# PixelScreen_WS2812B_4layer.net
KiCad netlist of a schematic drawn in EasyEDA Pro
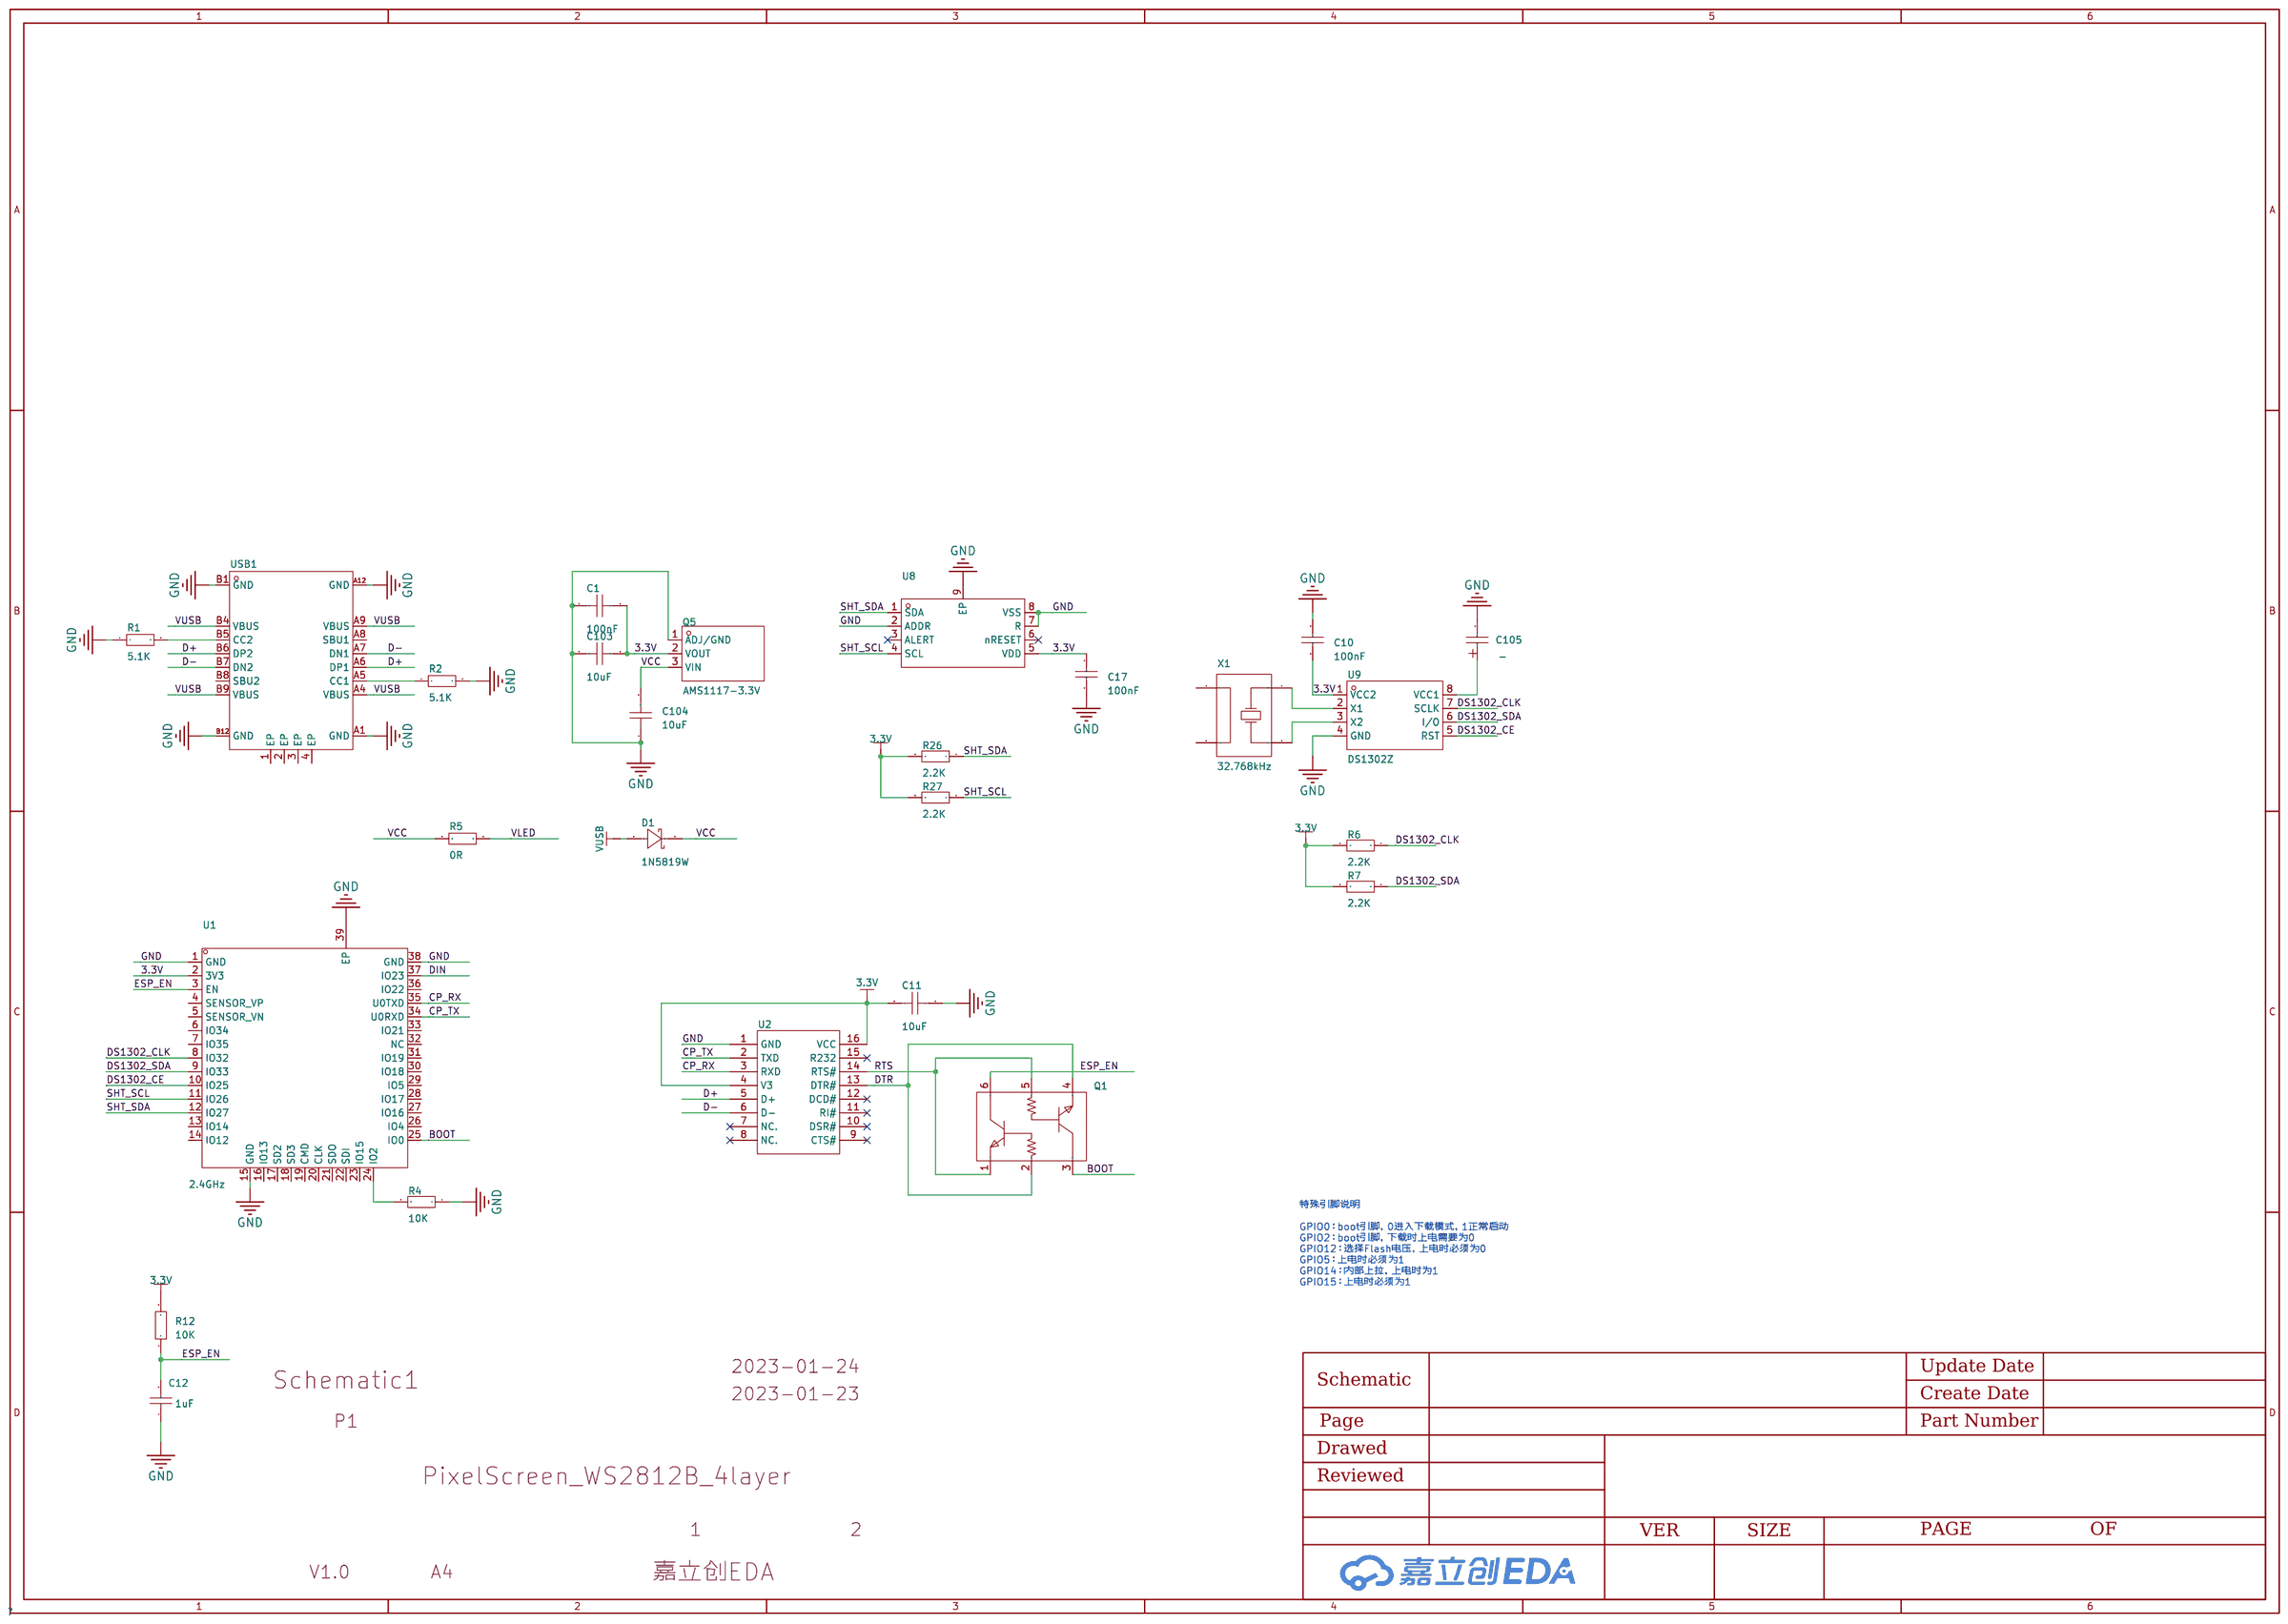
[diagram p0: P1]
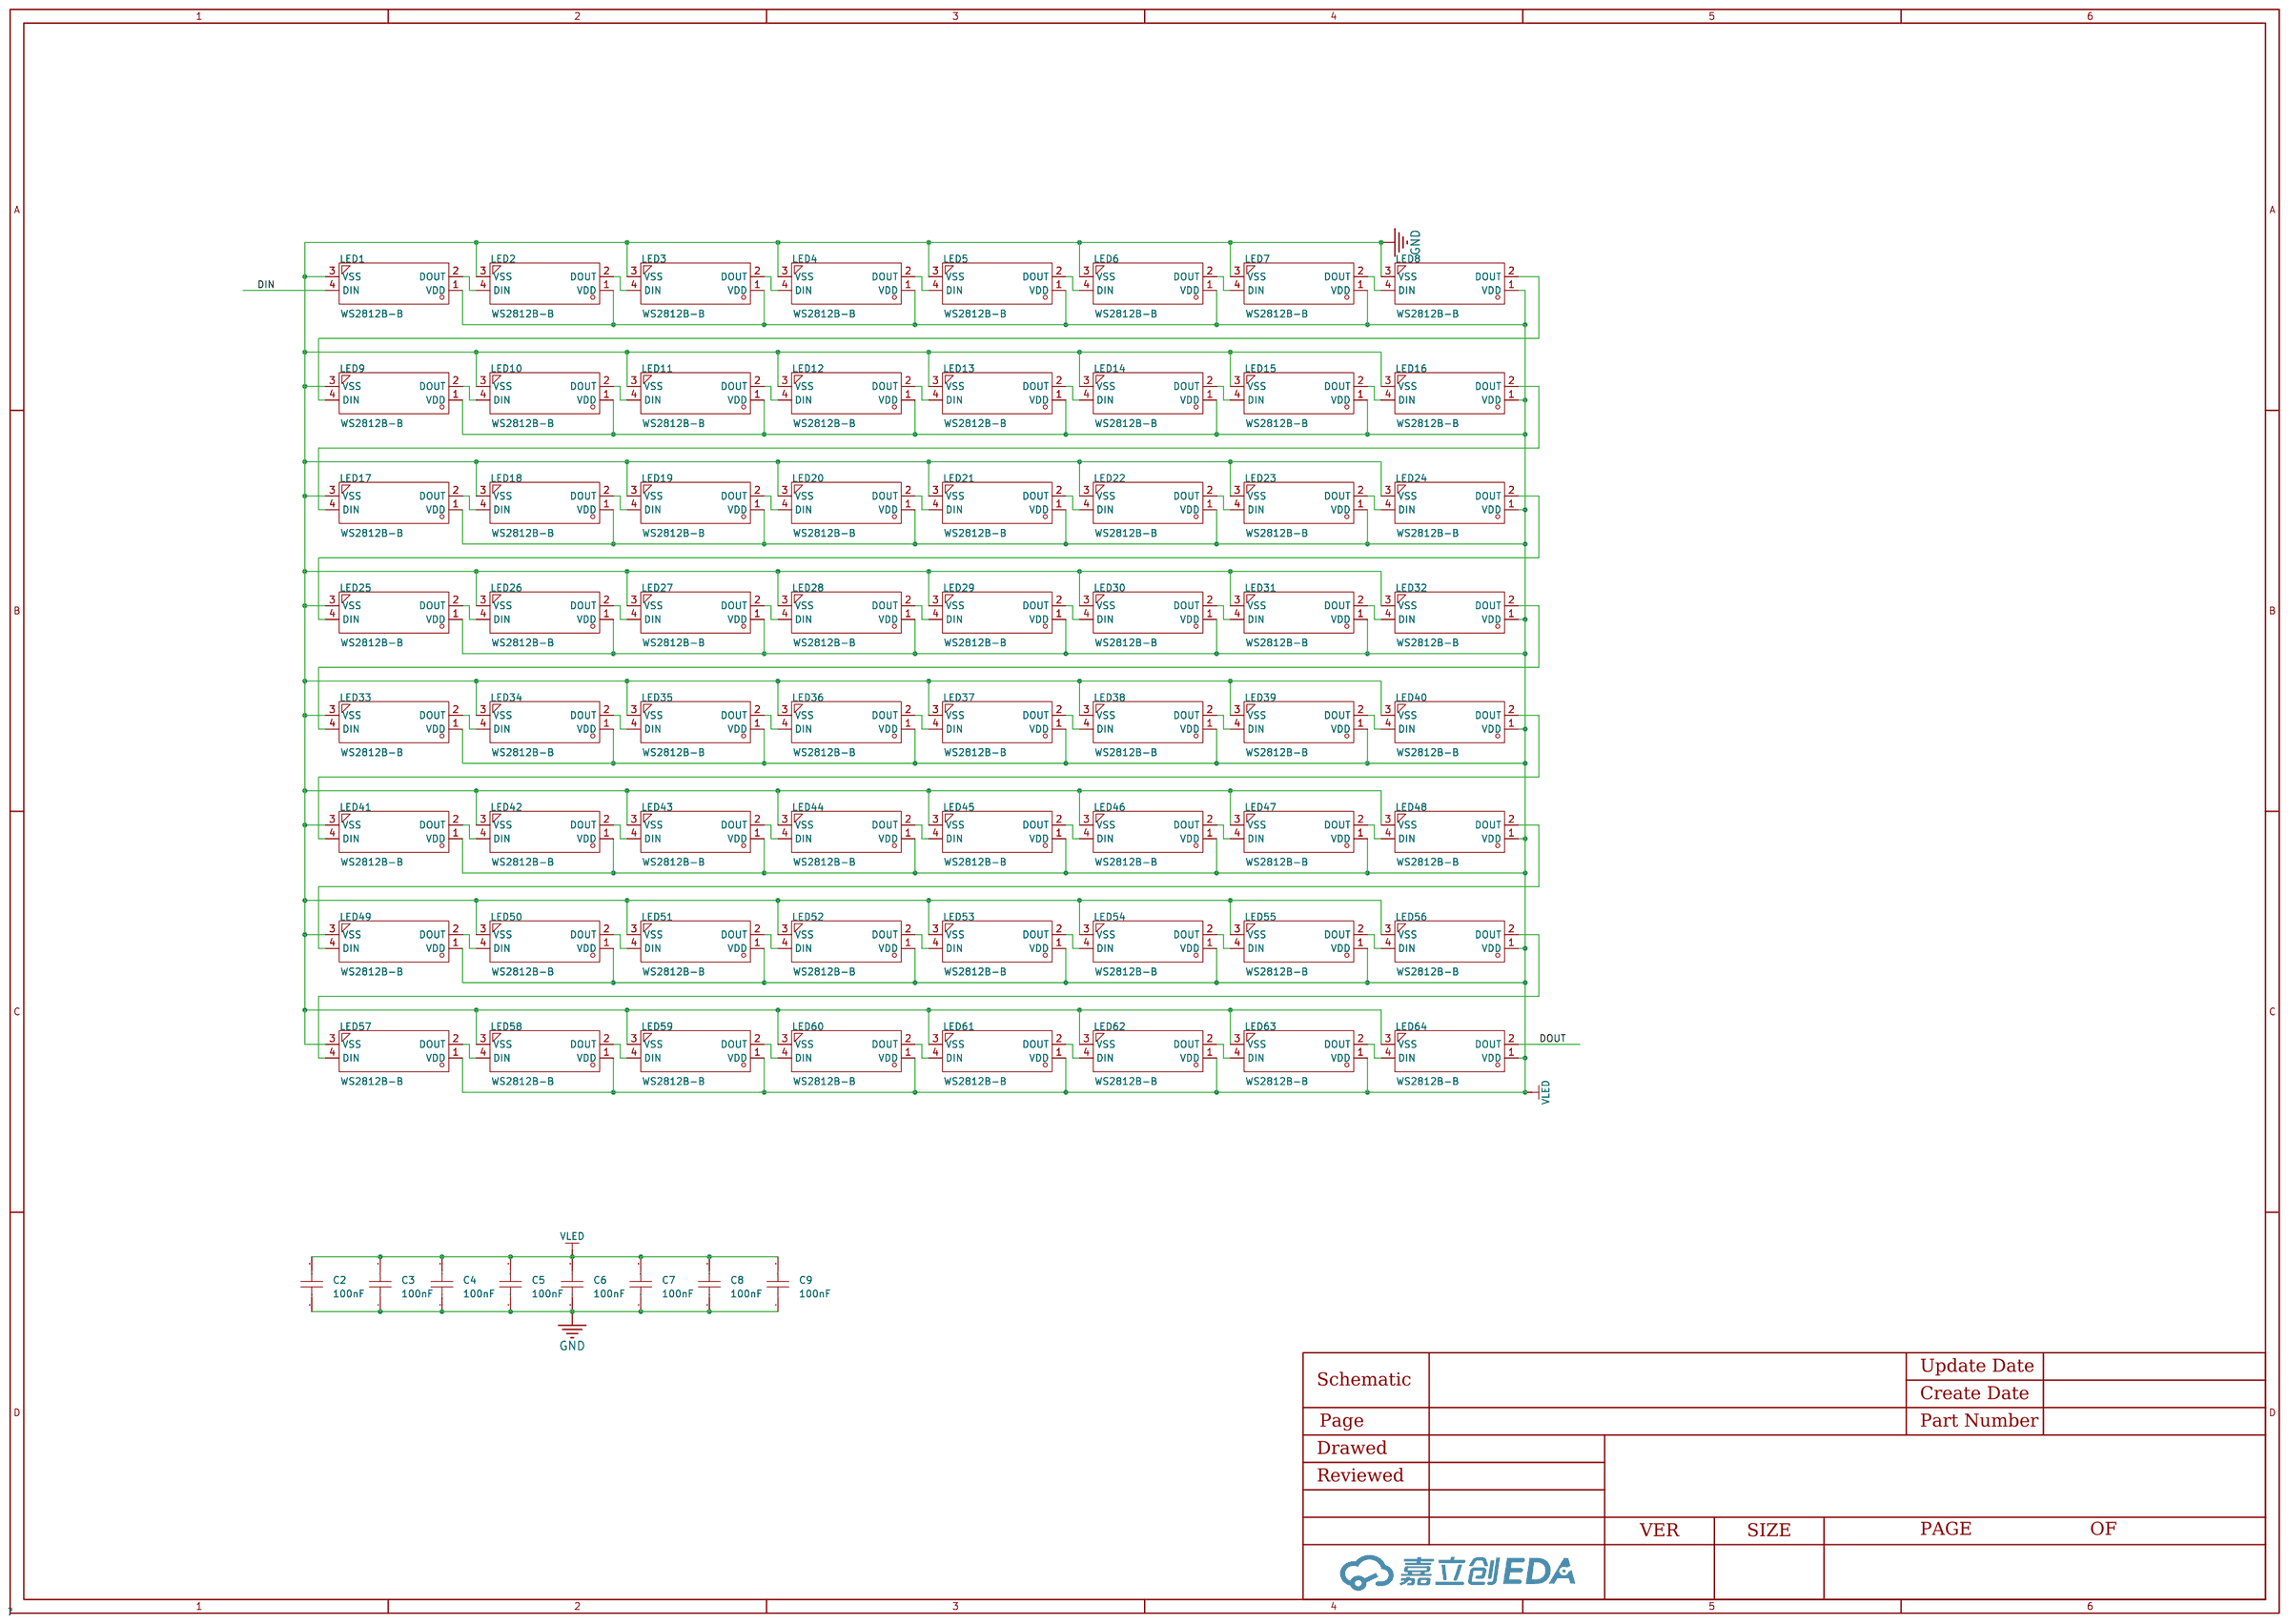
[diagram p1: P2]

(export (version "E")
  (design (tool "Eeschema 10.0.6"))
  (components
    (comp (ref "C1")
      (value "100nF")
      (footprint "easyedapro:C0603")
      (libsource (lib "easyedapro") (part "CapAcitance"))
    )
    (comp (ref "C10")
      (value "100nF")
      (footprint "easyedapro:C0402_NEW")
      (description "容值:100nF;精度:±10%;额定电压:16V;材质(温度系数):X7R;")
      (fields
        (field (name "Manufacturer Part") "CL05B104KO5NNNC")
        (field (name "Manufacturer") "SAMSUNG(三星)")
      )
      (libsource (lib "easyedapro") (part "CL05B104KO5NNNC"))
    )
    (comp (ref "C11")
      (value "10uF")
      (footprint "easyedapro:C0603")
      (libsource (lib "easyedapro") (part "CapAcitance"))
    )
    (comp (ref "C12")
      (value "1uF")
      (footprint "easyedapro:C0402_NEW")
      (description "容值:100nF;精度:±10%;额定电压:16V;材质(温度系数):X7R;")
      (fields
        (field (name "Manufacturer Part") "CL05B104KO5NNNC")
        (field (name "Manufacturer") "SAMSUNG(三星)")
      )
      (libsource (lib "easyedapro") (part "CL05B104KO5NNNC"))
    )
    (comp (ref "C17")
      (value "100nF")
      (footprint "easyedapro:C0402_NEW")
      (description "容值:100nF;精度:±10%;额定电压:16V;材质(温度系数):X7R;")
      (fields
        (field (name "Manufacturer Part") "CL05B104KO5NNNC")
        (field (name "Manufacturer") "SAMSUNG(三星)")
      )
      (libsource (lib "easyedapro") (part "CL05B104KO5NNNC"))
    )
    (comp (ref "C103")
      (value "10uF")
      (footprint "easyedapro:C0603")
      (libsource (lib "easyedapro") (part "CapAcitance"))
    )
    (comp (ref "C104")
      (value "10uF")
      (footprint "easyedapro:C0603")
      (libsource (lib "easyedapro") (part "CapAcitance"))
    )
    (comp (ref "C105")
      (value "-")
      (footprint "easyedapro:CAP-TH_DMS3R3224")
      (description "容值:-;精度:-;额定电压:-;等效串联电阻:-;漏电流:-;工作寿命:-;循环寿命:-;工作温度:-;电容体直径:-;电容体高:-;")
      (fields (field (name "Manufacturer Part") "DMS3R3224R") (field (name "Manufacturer") "KORCHIP(高奇普)"))
      (libsource (lib "easyedapro") (part "DMS3R3224"))
    )
    (comp (ref "D1")
      (value "1N5819W")
      (footprint "easyedapro:SOD-123_L2.7-W1.6-LS3.7-RD-1")
      (description "二极管配置:-;直流反向耐压(Vr):40V;平均整流电流(Io):1A;正向压降(Vf):900mV@3A;反向电流(Ir):1mA@40V;")
      (fields (field (name "Manufacturer") "TECH PUBLIC(台舟)"))
      (libsource (lib "easyedapro") (part "1N5819W_C2905650"))
    )
    (comp (ref "Q1")
      (value "UMH3N")
      (footprint "easyedapro:SC-70-6_L2.2-W1.3-P0.65-LS2.1-BR")
      (description "晶体管类型:2个NPN-预偏置;功率(Pd):150mW;集电极电流(Ic):100mA;集射极击穿电压(Vceo):50V;")
      (fields (field (name "Manufacturer") "CJ(江苏长电/长晶)"))
      (libsource (lib "easyedapro") (part "UMH3N"))
    )
    (comp (ref "Q5")
      (value "AMS1117-3.3V")
      (footprint "easyedapro:SOT-89-3_L4.5-W2.5-P1.50-LS4.2-BR")
      (description "输出类型:固定;输出极性:正;输出通道数:1;最大输入电压:18V;输出电压:3.3V;压差:1.4V@(1A);静态电流(地电流):12mA;输出电流:1A;工作温度:0℃~+125℃;")
      (fields (field (name "Manufacturer") "MSKSEMI(美森科)"))
      (libsource (lib "easyedapro") (part "AMS1117-3.3V_C5120796"))
    )
    (comp (ref "R1") (value "5.1K") (footprint "easyedapro:R0402") (libsource (lib "easyedapro") (part "电阻")))
    (comp (ref "R2") (value "5.1K") (footprint "easyedapro:R0402") (libsource (lib "easyedapro") (part "电阻")))
    (comp (ref "R4") (value "10K") (footprint "easyedapro:R0402") (libsource (lib "easyedapro") (part "电阻")))
    (comp (ref "R5") (value "0R") (footprint "easyedapro:R0402") (libsource (lib "easyedapro") (part "电阻")))
    (comp (ref "R6") (value "2.2K") (footprint "easyedapro:R0402") (libsource (lib "easyedapro") (part "电阻")))
    (comp (ref "R7") (value "2.2K") (footprint "easyedapro:R0402") (libsource (lib "easyedapro") (part "电阻")))
    (comp (ref "R12") (value "10K") (footprint "easyedapro:R0402") (libsource (lib "easyedapro") (part "电阻")))
    (comp (ref "R26")
      (value "2.2K")
      (footprint "easyedapro:R0402")
      (libsource (lib "easyedapro") (part "电阻"))
    )
    (comp (ref "R27")
      (value "2.2K")
      (footprint "easyedapro:R0402")
      (libsource (lib "easyedapro") (part "电阻"))
    )
    (comp (ref "U1")
      (value "2.4GHz")
      (footprint "easyedapro:WIRELM-SMD_ESP32-S")
      (description "频率:2.4GHz;发射功率:17dBm;核心处理器:LX6;天线形式:板载 PCB 天线/外接 IPEX;接收灵敏度:-90dBm;")
      (fields (field (name "Manufacturer Part") "ESP32-S") (field (name "Manufacturer") "Ai-Thinker(安信可)"))
      (libsource (lib "easyedapro") (part "ESP32-S"))
    )
    (comp (ref "U2")
      (value "CH340C")
      (footprint "easyedapro:SOP-16_L10.0-W3.9-P1.27-LS6.0-BL")
      (description "类型:Transceiver;协议类别:USB 2.0;驱动器/接收器数:-;数据速率:2Mbps;")
      (fields (field (name "Manufacturer") "WCH(南京沁恒)"))
      (libsource (lib "easyedapro") (part "CH340C"))
    )
    (comp (ref "U8")
      (value "~")
      (footprint "easyedapro:DFN-8_L2.5-W2.5-P0.50-BL-EP")
      (description "传感器类型:-;输出类型:-;温度范围:-;湿度范围:-;精度:-;")
      (fields
        (field (name "Manufacturer Part") "SHT30-DIS-B10KS")
        (field (name "Manufacturer") "Sensirion(瑞士盛思锐)")
      )
      (libsource (lib "easyedapro") (part "SHT30-DIS-B10KS"))
    )
    (comp (ref "U9")
      (value "DS1302Z")
      (footprint "easyedapro:SOP-8_L4.9-W3.9-P1.27-LS6.0-BL-1")
      (fields (field (name "Manufacturer") "JSMSEMI(杰盛微)"))
      (libsource (lib "easyedapro") (part "DS1302Z"))
    )
    (comp (ref "USB1")
      (value "~")
      (footprint "easyedapro:USB-C-SMD_KH-TYPE-C-16P")
      (fields (field (name "Manufacturer Part") "typec"))
      (libsource (lib "easyedapro") (part "TYPEC_C9900016956"))
    )
    (comp (ref "X1")
      (value "32.768kHz")
      (footprint "easyedapro:MC-146_4P-L6.7-W1.5-P0.85-TL")
      (description "晶振类型:贴片无源晶振;频率:32.768kHz;频率公差:±20ppm;负载电容:7pF;等效串联电阻(ESR):65kΩ;工作温度:-40℃~+85℃;")
      (fields
        (field (name "Manufacturer Part") "MC-14632.768kHz7.0pF20PPM")
        (field (name "Manufacturer") "EPSON(爱普生)")
      )
      (libsource (lib "easyedapro") (part "MC-14632.768kHz7.0pF20PPM"))
    )
    (comp (ref "C2")
      (value "100nF")
      (footprint "easyedapro:C0603")
      (libsource (lib "easyedapro") (part "CapAcitance"))
    )
    (comp (ref "C3")
      (value "100nF")
      (footprint "easyedapro:C0603")
      (libsource (lib "easyedapro") (part "CapAcitance"))
    )
    (comp (ref "C4")
      (value "100nF")
      (footprint "easyedapro:C0603")
      (libsource (lib "easyedapro") (part "CapAcitance"))
    )
    (comp (ref "C5")
      (value "100nF")
      (footprint "easyedapro:C0603")
      (libsource (lib "easyedapro") (part "CapAcitance"))
    )
    (comp (ref "C6")
      (value "100nF")
      (footprint "easyedapro:C0603")
      (libsource (lib "easyedapro") (part "CapAcitance"))
    )
    (comp (ref "C7")
      (value "100nF")
      (footprint "easyedapro:C0603")
      (libsource (lib "easyedapro") (part "CapAcitance"))
    )
    (comp (ref "C8")
      (value "100nF")
      (footprint "easyedapro:C0603")
      (libsource (lib "easyedapro") (part "CapAcitance"))
    )
    (comp (ref "C9")
      (value "100nF")
      (footprint "easyedapro:C0603")
      (libsource (lib "easyedapro") (part "CapAcitance"))
    )
    (comp (ref "LED1")
      (value "WS2812B-B")
      (footprint "easyedapro:LED-SMD_4P-L5.0-W5.0-BL_TC5050RGB")
      (description "发光颜色:RGB三色;")
      (fields (field (name "Manufacturer") "worldsemi"))
      (libsource (lib "easyedapro") (part "WS2812B-B"))
    )
    (comp (ref "LED2")
      (value "WS2812B-B")
      (footprint "easyedapro:LED-SMD_4P-L5.0-W5.0-BL_TC5050RGB")
      (description "发光颜色:RGB三色;")
      (fields (field (name "Manufacturer") "worldsemi"))
      (libsource (lib "easyedapro") (part "WS2812B-B"))
    )
    (comp (ref "LED3")
      (value "WS2812B-B")
      (footprint "easyedapro:LED-SMD_4P-L5.0-W5.0-BL_TC5050RGB")
      (description "发光颜色:RGB三色;")
      (fields (field (name "Manufacturer") "worldsemi"))
      (libsource (lib "easyedapro") (part "WS2812B-B"))
    )
    (comp (ref "LED4")
      (value "WS2812B-B")
      (footprint "easyedapro:LED-SMD_4P-L5.0-W5.0-BL_TC5050RGB")
      (description "发光颜色:RGB三色;")
      (fields (field (name "Manufacturer") "worldsemi"))
      (libsource (lib "easyedapro") (part "WS2812B-B"))
    )
    (comp (ref "LED5")
      (value "WS2812B-B")
      (footprint "easyedapro:LED-SMD_4P-L5.0-W5.0-BL_TC5050RGB")
      (description "发光颜色:RGB三色;")
      (fields (field (name "Manufacturer") "worldsemi"))
      (libsource (lib "easyedapro") (part "WS2812B-B"))
    )
    (comp (ref "LED6")
      (value "WS2812B-B")
      (footprint "easyedapro:LED-SMD_4P-L5.0-W5.0-BL_TC5050RGB")
      (description "发光颜色:RGB三色;")
      (fields (field (name "Manufacturer") "worldsemi"))
      (libsource (lib "easyedapro") (part "WS2812B-B"))
    )
    (comp (ref "LED7")
      (value "WS2812B-B")
      (footprint "easyedapro:LED-SMD_4P-L5.0-W5.0-BL_TC5050RGB")
      (description "发光颜色:RGB三色;")
      (fields (field (name "Manufacturer") "worldsemi"))
      (libsource (lib "easyedapro") (part "WS2812B-B"))
    )
    (comp (ref "LED8")
      (value "WS2812B-B")
      (footprint "easyedapro:LED-SMD_4P-L5.0-W5.0-BL_TC5050RGB")
      (description "发光颜色:RGB三色;")
      (fields (field (name "Manufacturer") "worldsemi"))
      (libsource (lib "easyedapro") (part "WS2812B-B"))
    )
    (comp (ref "LED9")
      (value "WS2812B-B")
      (footprint "easyedapro:LED-SMD_4P-L5.0-W5.0-BL_TC5050RGB")
      (description "发光颜色:RGB三色;")
      (fields (field (name "Manufacturer") "worldsemi"))
      (libsource (lib "easyedapro") (part "WS2812B-B"))
    )
    (comp (ref "LED10")
      (value "WS2812B-B")
      (footprint "easyedapro:LED-SMD_4P-L5.0-W5.0-BL_TC5050RGB")
      (description "发光颜色:RGB三色;")
      (fields (field (name "Manufacturer") "worldsemi"))
      (libsource (lib "easyedapro") (part "WS2812B-B"))
    )
    (comp (ref "LED11")
      (value "WS2812B-B")
      (footprint "easyedapro:LED-SMD_4P-L5.0-W5.0-BL_TC5050RGB")
      (description "发光颜色:RGB三色;")
      (fields (field (name "Manufacturer") "worldsemi"))
      (libsource (lib "easyedapro") (part "WS2812B-B"))
    )
    (comp (ref "LED12")
      (value "WS2812B-B")
      (footprint "easyedapro:LED-SMD_4P-L5.0-W5.0-BL_TC5050RGB")
      (description "发光颜色:RGB三色;")
      (fields (field (name "Manufacturer") "worldsemi"))
      (libsource (lib "easyedapro") (part "WS2812B-B"))
    )
    (comp (ref "LED13")
      (value "WS2812B-B")
      (footprint "easyedapro:LED-SMD_4P-L5.0-W5.0-BL_TC5050RGB")
      (description "发光颜色:RGB三色;")
      (fields (field (name "Manufacturer") "worldsemi"))
      (libsource (lib "easyedapro") (part "WS2812B-B"))
    )
    (comp (ref "LED14")
      (value "WS2812B-B")
      (footprint "easyedapro:LED-SMD_4P-L5.0-W5.0-BL_TC5050RGB")
      (description "发光颜色:RGB三色;")
      (fields (field (name "Manufacturer") "worldsemi"))
      (libsource (lib "easyedapro") (part "WS2812B-B"))
    )
    (comp (ref "LED15")
      (value "WS2812B-B")
      (footprint "easyedapro:LED-SMD_4P-L5.0-W5.0-BL_TC5050RGB")
      (description "发光颜色:RGB三色;")
      (fields (field (name "Manufacturer") "worldsemi"))
      (libsource (lib "easyedapro") (part "WS2812B-B"))
    )
    (comp (ref "LED16")
      (value "WS2812B-B")
      (footprint "easyedapro:LED-SMD_4P-L5.0-W5.0-BL_TC5050RGB")
      (description "发光颜色:RGB三色;")
      (fields (field (name "Manufacturer") "worldsemi"))
      (libsource (lib "easyedapro") (part "WS2812B-B"))
    )
    (comp (ref "LED17")
      (value "WS2812B-B")
      (footprint "easyedapro:LED-SMD_4P-L5.0-W5.0-BL_TC5050RGB")
      (description "发光颜色:RGB三色;")
      (fields (field (name "Manufacturer") "worldsemi"))
      (libsource (lib "easyedapro") (part "WS2812B-B"))
    )
    (comp (ref "LED18")
      (value "WS2812B-B")
      (footprint "easyedapro:LED-SMD_4P-L5.0-W5.0-BL_TC5050RGB")
      (description "发光颜色:RGB三色;")
      (fields (field (name "Manufacturer") "worldsemi"))
      (libsource (lib "easyedapro") (part "WS2812B-B"))
    )
    (comp (ref "LED19")
      (value "WS2812B-B")
      (footprint "easyedapro:LED-SMD_4P-L5.0-W5.0-BL_TC5050RGB")
      (description "发光颜色:RGB三色;")
      (fields (field (name "Manufacturer") "worldsemi"))
      (libsource (lib "easyedapro") (part "WS2812B-B"))
    )
    (comp (ref "LED20")
      (value "WS2812B-B")
      (footprint "easyedapro:LED-SMD_4P-L5.0-W5.0-BL_TC5050RGB")
      (description "发光颜色:RGB三色;")
      (fields (field (name "Manufacturer") "worldsemi"))
      (libsource (lib "easyedapro") (part "WS2812B-B"))
    )
    (comp (ref "LED21")
      (value "WS2812B-B")
      (footprint "easyedapro:LED-SMD_4P-L5.0-W5.0-BL_TC5050RGB")
      (description "发光颜色:RGB三色;")
      (fields (field (name "Manufacturer") "worldsemi"))
      (libsource (lib "easyedapro") (part "WS2812B-B"))
    )
    (comp (ref "LED22")
      (value "WS2812B-B")
      (footprint "easyedapro:LED-SMD_4P-L5.0-W5.0-BL_TC5050RGB")
      (description "发光颜色:RGB三色;")
      (fields (field (name "Manufacturer") "worldsemi"))
      (libsource (lib "easyedapro") (part "WS2812B-B"))
    )
    (comp (ref "LED23")
      (value "WS2812B-B")
      (footprint "easyedapro:LED-SMD_4P-L5.0-W5.0-BL_TC5050RGB")
      (description "发光颜色:RGB三色;")
      (fields (field (name "Manufacturer") "worldsemi"))
      (libsource (lib "easyedapro") (part "WS2812B-B"))
    )
    (comp (ref "LED24")
      (value "WS2812B-B")
      (footprint "easyedapro:LED-SMD_4P-L5.0-W5.0-BL_TC5050RGB")
      (description "发光颜色:RGB三色;")
      (fields (field (name "Manufacturer") "worldsemi"))
      (libsource (lib "easyedapro") (part "WS2812B-B"))
    )
    (comp (ref "LED25")
      (value "WS2812B-B")
      (footprint "easyedapro:LED-SMD_4P-L5.0-W5.0-BL_TC5050RGB")
      (description "发光颜色:RGB三色;")
      (fields (field (name "Manufacturer") "worldsemi"))
      (libsource (lib "easyedapro") (part "WS2812B-B"))
    )
    (comp (ref "LED26")
      (value "WS2812B-B")
      (footprint "easyedapro:LED-SMD_4P-L5.0-W5.0-BL_TC5050RGB")
      (description "发光颜色:RGB三色;")
      (fields (field (name "Manufacturer") "worldsemi"))
      (libsource (lib "easyedapro") (part "WS2812B-B"))
    )
    (comp (ref "LED27")
      (value "WS2812B-B")
      (footprint "easyedapro:LED-SMD_4P-L5.0-W5.0-BL_TC5050RGB")
      (description "发光颜色:RGB三色;")
      (fields (field (name "Manufacturer") "worldsemi"))
      (libsource (lib "easyedapro") (part "WS2812B-B"))
    )
    (comp (ref "LED28")
      (value "WS2812B-B")
      (footprint "easyedapro:LED-SMD_4P-L5.0-W5.0-BL_TC5050RGB")
      (description "发光颜色:RGB三色;")
      (fields (field (name "Manufacturer") "worldsemi"))
      (libsource (lib "easyedapro") (part "WS2812B-B"))
    )
    (comp (ref "LED29")
      (value "WS2812B-B")
      (footprint "easyedapro:LED-SMD_4P-L5.0-W5.0-BL_TC5050RGB")
      (description "发光颜色:RGB三色;")
      (fields (field (name "Manufacturer") "worldsemi"))
      (libsource (lib "easyedapro") (part "WS2812B-B"))
    )
    (comp (ref "LED30")
      (value "WS2812B-B")
      (footprint "easyedapro:LED-SMD_4P-L5.0-W5.0-BL_TC5050RGB")
      (description "发光颜色:RGB三色;")
      (fields (field (name "Manufacturer") "worldsemi"))
      (libsource (lib "easyedapro") (part "WS2812B-B"))
    )
    (comp (ref "LED31")
      (value "WS2812B-B")
      (footprint "easyedapro:LED-SMD_4P-L5.0-W5.0-BL_TC5050RGB")
      (description "发光颜色:RGB三色;")
      (fields (field (name "Manufacturer") "worldsemi"))
      (libsource (lib "easyedapro") (part "WS2812B-B"))
    )
    (comp (ref "LED32")
      (value "WS2812B-B")
      (footprint "easyedapro:LED-SMD_4P-L5.0-W5.0-BL_TC5050RGB")
      (description "发光颜色:RGB三色;")
      (fields (field (name "Manufacturer") "worldsemi"))
      (libsource (lib "easyedapro") (part "WS2812B-B"))
    )
    (comp (ref "LED33")
      (value "WS2812B-B")
      (footprint "easyedapro:LED-SMD_4P-L5.0-W5.0-BL_TC5050RGB")
      (description "发光颜色:RGB三色;")
      (fields (field (name "Manufacturer") "worldsemi"))
      (libsource (lib "easyedapro") (part "WS2812B-B"))
    )
    (comp (ref "LED34")
      (value "WS2812B-B")
      (footprint "easyedapro:LED-SMD_4P-L5.0-W5.0-BL_TC5050RGB")
      (description "发光颜色:RGB三色;")
      (fields (field (name "Manufacturer") "worldsemi"))
      (libsource (lib "easyedapro") (part "WS2812B-B"))
    )
    (comp (ref "LED35")
      (value "WS2812B-B")
      (footprint "easyedapro:LED-SMD_4P-L5.0-W5.0-BL_TC5050RGB")
      (description "发光颜色:RGB三色;")
      (fields (field (name "Manufacturer") "worldsemi"))
      (libsource (lib "easyedapro") (part "WS2812B-B"))
    )
    (comp (ref "LED36")
      (value "WS2812B-B")
      (footprint "easyedapro:LED-SMD_4P-L5.0-W5.0-BL_TC5050RGB")
      (description "发光颜色:RGB三色;")
      (fields (field (name "Manufacturer") "worldsemi"))
      (libsource (lib "easyedapro") (part "WS2812B-B"))
    )
    (comp (ref "LED37")
      (value "WS2812B-B")
      (footprint "easyedapro:LED-SMD_4P-L5.0-W5.0-BL_TC5050RGB")
      (description "发光颜色:RGB三色;")
      (fields (field (name "Manufacturer") "worldsemi"))
      (libsource (lib "easyedapro") (part "WS2812B-B"))
    )
    (comp (ref "LED38")
      (value "WS2812B-B")
      (footprint "easyedapro:LED-SMD_4P-L5.0-W5.0-BL_TC5050RGB")
      (description "发光颜色:RGB三色;")
      (fields (field (name "Manufacturer") "worldsemi"))
      (libsource (lib "easyedapro") (part "WS2812B-B"))
    )
    (comp (ref "LED39")
      (value "WS2812B-B")
      (footprint "easyedapro:LED-SMD_4P-L5.0-W5.0-BL_TC5050RGB")
      (description "发光颜色:RGB三色;")
      (fields (field (name "Manufacturer") "worldsemi"))
      (libsource (lib "easyedapro") (part "WS2812B-B"))
    )
    (comp (ref "LED40")
      (value "WS2812B-B")
      (footprint "easyedapro:LED-SMD_4P-L5.0-W5.0-BL_TC5050RGB")
      (description "发光颜色:RGB三色;")
      (fields (field (name "Manufacturer") "worldsemi"))
      (libsource (lib "easyedapro") (part "WS2812B-B"))
    )
    (comp (ref "LED41")
      (value "WS2812B-B")
      (footprint "easyedapro:LED-SMD_4P-L5.0-W5.0-BL_TC5050RGB")
      (description "发光颜色:RGB三色;")
      (fields (field (name "Manufacturer") "worldsemi"))
      (libsource (lib "easyedapro") (part "WS2812B-B"))
    )
    (comp (ref "LED42")
      (value "WS2812B-B")
      (footprint "easyedapro:LED-SMD_4P-L5.0-W5.0-BL_TC5050RGB")
      (description "发光颜色:RGB三色;")
      (fields (field (name "Manufacturer") "worldsemi"))
      (libsource (lib "easyedapro") (part "WS2812B-B"))
    )
    (comp (ref "LED43")
      (value "WS2812B-B")
      (footprint "easyedapro:LED-SMD_4P-L5.0-W5.0-BL_TC5050RGB")
      (description "发光颜色:RGB三色;")
      (fields (field (name "Manufacturer") "worldsemi"))
      (libsource (lib "easyedapro") (part "WS2812B-B"))
    )
    (comp (ref "LED44")
      (value "WS2812B-B")
      (footprint "easyedapro:LED-SMD_4P-L5.0-W5.0-BL_TC5050RGB")
      (description "发光颜色:RGB三色;")
      (fields (field (name "Manufacturer") "worldsemi"))
      (libsource (lib "easyedapro") (part "WS2812B-B"))
    )
    (comp (ref "LED45")
      (value "WS2812B-B")
      (footprint "easyedapro:LED-SMD_4P-L5.0-W5.0-BL_TC5050RGB")
      (description "发光颜色:RGB三色;")
      (fields (field (name "Manufacturer") "worldsemi"))
      (libsource (lib "easyedapro") (part "WS2812B-B"))
    )
    (comp (ref "LED46")
      (value "WS2812B-B")
      (footprint "easyedapro:LED-SMD_4P-L5.0-W5.0-BL_TC5050RGB")
      (description "发光颜色:RGB三色;")
      (fields (field (name "Manufacturer") "worldsemi"))
      (libsource (lib "easyedapro") (part "WS2812B-B"))
    )
    (comp (ref "LED47")
      (value "WS2812B-B")
      (footprint "easyedapro:LED-SMD_4P-L5.0-W5.0-BL_TC5050RGB")
      (description "发光颜色:RGB三色;")
      (fields (field (name "Manufacturer") "worldsemi"))
      (libsource (lib "easyedapro") (part "WS2812B-B"))
    )
    (comp (ref "LED48")
      (value "WS2812B-B")
      (footprint "easyedapro:LED-SMD_4P-L5.0-W5.0-BL_TC5050RGB")
      (description "发光颜色:RGB三色;")
      (fields (field (name "Manufacturer") "worldsemi"))
      (libsource (lib "easyedapro") (part "WS2812B-B"))
    )
    (comp (ref "LED49")
      (value "WS2812B-B")
      (footprint "easyedapro:LED-SMD_4P-L5.0-W5.0-BL_TC5050RGB")
      (description "发光颜色:RGB三色;")
      (fields (field (name "Manufacturer") "worldsemi"))
      (libsource (lib "easyedapro") (part "WS2812B-B"))
    )
    (comp (ref "LED50")
      (value "WS2812B-B")
      (footprint "easyedapro:LED-SMD_4P-L5.0-W5.0-BL_TC5050RGB")
      (description "发光颜色:RGB三色;")
      (fields (field (name "Manufacturer") "worldsemi"))
      (libsource (lib "easyedapro") (part "WS2812B-B"))
    )
    (comp (ref "LED51")
      (value "WS2812B-B")
      (footprint "easyedapro:LED-SMD_4P-L5.0-W5.0-BL_TC5050RGB")
      (description "发光颜色:RGB三色;")
      (fields (field (name "Manufacturer") "worldsemi"))
      (libsource (lib "easyedapro") (part "WS2812B-B"))
    )
    (comp (ref "LED52")
      (value "WS2812B-B")
      (footprint "easyedapro:LED-SMD_4P-L5.0-W5.0-BL_TC5050RGB")
      (description "发光颜色:RGB三色;")
      (fields (field (name "Manufacturer") "worldsemi"))
      (libsource (lib "easyedapro") (part "WS2812B-B"))
    )
    (comp (ref "LED53")
      (value "WS2812B-B")
      (footprint "easyedapro:LED-SMD_4P-L5.0-W5.0-BL_TC5050RGB")
      (description "发光颜色:RGB三色;")
      (fields (field (name "Manufacturer") "worldsemi"))
      (libsource (lib "easyedapro") (part "WS2812B-B"))
    )
    (comp (ref "LED54")
      (value "WS2812B-B")
      (footprint "easyedapro:LED-SMD_4P-L5.0-W5.0-BL_TC5050RGB")
      (description "发光颜色:RGB三色;")
      (fields (field (name "Manufacturer") "worldsemi"))
      (libsource (lib "easyedapro") (part "WS2812B-B"))
    )
    (comp (ref "LED55")
      (value "WS2812B-B")
      (footprint "easyedapro:LED-SMD_4P-L5.0-W5.0-BL_TC5050RGB")
      (description "发光颜色:RGB三色;")
      (fields (field (name "Manufacturer") "worldsemi"))
      (libsource (lib "easyedapro") (part "WS2812B-B"))
    )
    (comp (ref "LED56")
      (value "WS2812B-B")
      (footprint "easyedapro:LED-SMD_4P-L5.0-W5.0-BL_TC5050RGB")
      (description "发光颜色:RGB三色;")
      (fields (field (name "Manufacturer") "worldsemi"))
      (libsource (lib "easyedapro") (part "WS2812B-B"))
    )
    (comp (ref "LED57")
      (value "WS2812B-B")
      (footprint "easyedapro:LED-SMD_4P-L5.0-W5.0-BL_TC5050RGB")
      (description "发光颜色:RGB三色;")
      (fields (field (name "Manufacturer") "worldsemi"))
      (libsource (lib "easyedapro") (part "WS2812B-B"))
    )
    (comp (ref "LED58")
      (value "WS2812B-B")
      (footprint "easyedapro:LED-SMD_4P-L5.0-W5.0-BL_TC5050RGB")
      (description "发光颜色:RGB三色;")
      (fields (field (name "Manufacturer") "worldsemi"))
      (libsource (lib "easyedapro") (part "WS2812B-B"))
    )
    (comp (ref "LED59")
      (value "WS2812B-B")
      (footprint "easyedapro:LED-SMD_4P-L5.0-W5.0-BL_TC5050RGB")
      (description "发光颜色:RGB三色;")
      (fields (field (name "Manufacturer") "worldsemi"))
      (libsource (lib "easyedapro") (part "WS2812B-B"))
    )
    (comp (ref "LED60")
      (value "WS2812B-B")
      (footprint "easyedapro:LED-SMD_4P-L5.0-W5.0-BL_TC5050RGB")
      (description "发光颜色:RGB三色;")
      (fields (field (name "Manufacturer") "worldsemi"))
      (libsource (lib "easyedapro") (part "WS2812B-B"))
    )
    (comp (ref "LED61")
      (value "WS2812B-B")
      (footprint "easyedapro:LED-SMD_4P-L5.0-W5.0-BL_TC5050RGB")
      (description "发光颜色:RGB三色;")
      (fields (field (name "Manufacturer") "worldsemi"))
      (libsource (lib "easyedapro") (part "WS2812B-B"))
    )
    (comp (ref "LED62")
      (value "WS2812B-B")
      (footprint "easyedapro:LED-SMD_4P-L5.0-W5.0-BL_TC5050RGB")
      (description "发光颜色:RGB三色;")
      (fields (field (name "Manufacturer") "worldsemi"))
      (libsource (lib "easyedapro") (part "WS2812B-B"))
    )
    (comp (ref "LED63")
      (value "WS2812B-B")
      (footprint "easyedapro:LED-SMD_4P-L5.0-W5.0-BL_TC5050RGB")
      (description "发光颜色:RGB三色;")
      (fields (field (name "Manufacturer") "worldsemi"))
      (libsource (lib "easyedapro") (part "WS2812B-B"))
    )
    (comp (ref "LED64")
      (value "WS2812B-B")
      (footprint "easyedapro:LED-SMD_4P-L5.0-W5.0-BL_TC5050RGB")
      (description "发光颜色:RGB三色;")
      (fields (field (name "Manufacturer") "worldsemi"))
      (libsource (lib "easyedapro") (part "WS2812B-B"))
    )
  )
  (nets
    (net (code "1") (name "3.3V") (class "Default")
      (node (ref "C1") (pin "2") (pinfunction "2_2") (pintype "input"))
      (node (ref "C10") (pin "2") (pinfunction "2_2") (pintype "input"))
      (node (ref "C103") (pin "2") (pinfunction "2_2") (pintype "input"))
      (node (ref "C11") (pin "2") (pinfunction "2_2") (pintype "input"))
      (node (ref "C17") (pin "1") (pinfunction "1_1") (pintype "input"))
      (node (ref "Q5") (pin "2") (pinfunction "VOUT_2") (pintype "input"))
      (node (ref "R12") (pin "2") (pinfunction "2_2") (pintype "input"))
      (node (ref "R26") (pin "2") (pinfunction "2_2") (pintype "input"))
      (node (ref "R27") (pin "2") (pinfunction "2_2") (pintype "input"))
      (node (ref "R6") (pin "2") (pinfunction "2_2") (pintype "input"))
      (node (ref "R7") (pin "2") (pinfunction "2_2") (pintype "input"))
      (node (ref "U1") (pin "2") (pinfunction "3V3_2") (pintype "input"))
      (node (ref "U2") (pin "16") (pinfunction "VCC_16") (pintype "input"))
      (node (ref "U2") (pin "4") (pinfunction "V3_4") (pintype "input"))
      (node (ref "U8") (pin "5") (pinfunction "VDD_5") (pintype "input"))
      (node (ref "U9") (pin "1") (pinfunction "VCC2_1") (pintype "input"))
    )
    (net (code "2") (name "BOOT") (class "Default")
      (node (ref "Q1") (pin "3") (pinfunction "C_3") (pintype "input"))
      (node (ref "U1") (pin "25") (pinfunction "IO0_25") (pintype "input"))
    )
    (net (code "3") (name "CP_RX") (class "Default")
      (node (ref "U1") (pin "35") (pinfunction "U0TXD_35") (pintype "input"))
      (node (ref "U2") (pin "3") (pinfunction "RXD_3") (pintype "input"))
    )
    (net (code "4") (name "CP_TX") (class "Default")
      (node (ref "U1") (pin "34") (pinfunction "U0RXD_34") (pintype "input"))
      (node (ref "U2") (pin "2") (pinfunction "TXD_2") (pintype "input"))
    )
    (net (code "5") (name "D+") (class "Default")
      (node (ref "U2") (pin "5") (pinfunction "D+_5") (pintype "input"))
      (node (ref "USB1") (pin "A6") (pinfunction "DP1_A6") (pintype "input"))
      (node (ref "USB1") (pin "B6") (pinfunction "DP2_B6") (pintype "input"))
    )
    (net (code "6") (name "D-") (class "Default")
      (node (ref "U2") (pin "6") (pinfunction "D-_6") (pintype "input"))
      (node (ref "USB1") (pin "A7") (pinfunction "DN1_A7") (pintype "input"))
      (node (ref "USB1") (pin "B7") (pinfunction "DN2_B7") (pintype "input"))
    )
    (net (code "7") (name "DIN") (class "Default")
      (node (ref "LED1") (pin "4") (pinfunction "DIN_4") (pintype "input"))
      (node (ref "U1") (pin "37") (pinfunction "IO23_37") (pintype "input"))
    )
    (net (code "8") (name "DOUT") (class "Default")
      (node (ref "LED64") (pin "2") (pinfunction "DOUT_2") (pintype "input"))
    )
    (net (code "9") (name "DS1302_CE") (class "Default")
      (node (ref "U1") (pin "10") (pinfunction "IO25_10") (pintype "input"))
      (node (ref "U9") (pin "5") (pinfunction "RST_5") (pintype "input"))
    )
    (net (code "10") (name "DS1302_CLK") (class "Default")
      (node (ref "R6") (pin "1") (pinfunction "1_1") (pintype "input"))
      (node (ref "U1") (pin "8") (pinfunction "IO32_8") (pintype "input"))
      (node (ref "U9") (pin "7") (pinfunction "SCLK_7") (pintype "input"))
    )
    (net (code "11") (name "DS1302_SDA") (class "Default")
      (node (ref "R7") (pin "1") (pinfunction "1_1") (pintype "input"))
      (node (ref "U1") (pin "9") (pinfunction "IO33_9") (pintype "input"))
      (node (ref "U9") (pin "6") (pinfunction "I/O_6") (pintype "input"))
    )
    (net (code "12") (name "DTR") (class "Default")
      (node (ref "Q1") (pin "2") (pinfunction "B_2") (pintype "input"))
      (node (ref "Q1") (pin "4") (pinfunction "E_4") (pintype "input"))
      (node (ref "U2") (pin "13") (pinfunction "DTR#_13") (pintype "input"))
    )
    (net (code "13") (name "ESP_EN") (class "Default")
      (node (ref "C12") (pin "2") (pinfunction "2_2") (pintype "input"))
      (node (ref "Q1") (pin "6") (pinfunction "C_6") (pintype "input"))
      (node (ref "R12") (pin "1") (pinfunction "1_1") (pintype "input"))
      (node (ref "U1") (pin "3") (pinfunction "EN_3") (pintype "input"))
    )
    (net (code "14") (name "GND") (class "Default")
      (node (ref "C1") (pin "1") (pinfunction "1_1") (pintype "input"))
      (node (ref "C10") (pin "1") (pinfunction "1_1") (pintype "input"))
      (node (ref "C103") (pin "1") (pinfunction "1_1") (pintype "input"))
      (node (ref "C104") (pin "1") (pinfunction "1_1") (pintype "input"))
      (node (ref "C105") (pin "2") (pinfunction "2_2") (pintype "input"))
      (node (ref "C11") (pin "1") (pinfunction "1_1") (pintype "input"))
      (node (ref "C12") (pin "1") (pinfunction "1_1") (pintype "input"))
      (node (ref "C17") (pin "2") (pinfunction "2_2") (pintype "input"))
      (node (ref "C2") (pin "1") (pinfunction "1_1") (pintype "input"))
      (node (ref "C3") (pin "1") (pinfunction "1_1") (pintype "input"))
      (node (ref "C4") (pin "1") (pinfunction "1_1") (pintype "input"))
      (node (ref "C5") (pin "1") (pinfunction "1_1") (pintype "input"))
      (node (ref "C6") (pin "1") (pinfunction "1_1") (pintype "input"))
      (node (ref "C7") (pin "1") (pinfunction "1_1") (pintype "input"))
      (node (ref "C8") (pin "1") (pinfunction "1_1") (pintype "input"))
      (node (ref "C9") (pin "1") (pinfunction "1_1") (pintype "input"))
      (node (ref "LED1") (pin "3") (pinfunction "VSS_3") (pintype "input"))
      (node (ref "LED10") (pin "3") (pinfunction "VSS_3") (pintype "input"))
      (node (ref "LED11") (pin "3") (pinfunction "VSS_3") (pintype "input"))
      (node (ref "LED12") (pin "3") (pinfunction "VSS_3") (pintype "input"))
      (node (ref "LED13") (pin "3") (pinfunction "VSS_3") (pintype "input"))
      (node (ref "LED14") (pin "3") (pinfunction "VSS_3") (pintype "input"))
      (node (ref "LED15") (pin "3") (pinfunction "VSS_3") (pintype "input"))
      (node (ref "LED16") (pin "3") (pinfunction "VSS_3") (pintype "input"))
      (node (ref "LED17") (pin "3") (pinfunction "VSS_3") (pintype "input"))
      (node (ref "LED18") (pin "3") (pinfunction "VSS_3") (pintype "input"))
      (node (ref "LED19") (pin "3") (pinfunction "VSS_3") (pintype "input"))
      (node (ref "LED2") (pin "3") (pinfunction "VSS_3") (pintype "input"))
      (node (ref "LED20") (pin "3") (pinfunction "VSS_3") (pintype "input"))
      (node (ref "LED21") (pin "3") (pinfunction "VSS_3") (pintype "input"))
      (node (ref "LED22") (pin "3") (pinfunction "VSS_3") (pintype "input"))
      (node (ref "LED23") (pin "3") (pinfunction "VSS_3") (pintype "input"))
      (node (ref "LED24") (pin "3") (pinfunction "VSS_3") (pintype "input"))
      (node (ref "LED25") (pin "3") (pinfunction "VSS_3") (pintype "input"))
      (node (ref "LED26") (pin "3") (pinfunction "VSS_3") (pintype "input"))
      (node (ref "LED27") (pin "3") (pinfunction "VSS_3") (pintype "input"))
      (node (ref "LED28") (pin "3") (pinfunction "VSS_3") (pintype "input"))
      (node (ref "LED29") (pin "3") (pinfunction "VSS_3") (pintype "input"))
      (node (ref "LED3") (pin "3") (pinfunction "VSS_3") (pintype "input"))
      (node (ref "LED30") (pin "3") (pinfunction "VSS_3") (pintype "input"))
      (node (ref "LED31") (pin "3") (pinfunction "VSS_3") (pintype "input"))
      (node (ref "LED32") (pin "3") (pinfunction "VSS_3") (pintype "input"))
      (node (ref "LED33") (pin "3") (pinfunction "VSS_3") (pintype "input"))
      (node (ref "LED34") (pin "3") (pinfunction "VSS_3") (pintype "input"))
      (node (ref "LED35") (pin "3") (pinfunction "VSS_3") (pintype "input"))
      (node (ref "LED36") (pin "3") (pinfunction "VSS_3") (pintype "input"))
      (node (ref "LED37") (pin "3") (pinfunction "VSS_3") (pintype "input"))
      (node (ref "LED38") (pin "3") (pinfunction "VSS_3") (pintype "input"))
      (node (ref "LED39") (pin "3") (pinfunction "VSS_3") (pintype "input"))
      (node (ref "LED4") (pin "3") (pinfunction "VSS_3") (pintype "input"))
      (node (ref "LED40") (pin "3") (pinfunction "VSS_3") (pintype "input"))
      (node (ref "LED41") (pin "3") (pinfunction "VSS_3") (pintype "input"))
      (node (ref "LED42") (pin "3") (pinfunction "VSS_3") (pintype "input"))
      (node (ref "LED43") (pin "3") (pinfunction "VSS_3") (pintype "input"))
      (node (ref "LED44") (pin "3") (pinfunction "VSS_3") (pintype "input"))
      (node (ref "LED45") (pin "3") (pinfunction "VSS_3") (pintype "input"))
      (node (ref "LED46") (pin "3") (pinfunction "VSS_3") (pintype "input"))
      (node (ref "LED47") (pin "3") (pinfunction "VSS_3") (pintype "input"))
      (node (ref "LED48") (pin "3") (pinfunction "VSS_3") (pintype "input"))
      (node (ref "LED49") (pin "3") (pinfunction "VSS_3") (pintype "input"))
      (node (ref "LED5") (pin "3") (pinfunction "VSS_3") (pintype "input"))
      (node (ref "LED50") (pin "3") (pinfunction "VSS_3") (pintype "input"))
      (node (ref "LED51") (pin "3") (pinfunction "VSS_3") (pintype "input"))
      (node (ref "LED52") (pin "3") (pinfunction "VSS_3") (pintype "input"))
      (node (ref "LED53") (pin "3") (pinfunction "VSS_3") (pintype "input"))
      (node (ref "LED54") (pin "3") (pinfunction "VSS_3") (pintype "input"))
      (node (ref "LED55") (pin "3") (pinfunction "VSS_3") (pintype "input"))
      (node (ref "LED56") (pin "3") (pinfunction "VSS_3") (pintype "input"))
      (node (ref "LED57") (pin "3") (pinfunction "VSS_3") (pintype "input"))
      (node (ref "LED58") (pin "3") (pinfunction "VSS_3") (pintype "input"))
      (node (ref "LED59") (pin "3") (pinfunction "VSS_3") (pintype "input"))
      (node (ref "LED6") (pin "3") (pinfunction "VSS_3") (pintype "input"))
      (node (ref "LED60") (pin "3") (pinfunction "VSS_3") (pintype "input"))
      (node (ref "LED61") (pin "3") (pinfunction "VSS_3") (pintype "input"))
      (node (ref "LED62") (pin "3") (pinfunction "VSS_3") (pintype "input"))
      (node (ref "LED63") (pin "3") (pinfunction "VSS_3") (pintype "input"))
      (node (ref "LED64") (pin "3") (pinfunction "VSS_3") (pintype "input"))
      (node (ref "LED7") (pin "3") (pinfunction "VSS_3") (pintype "input"))
      (node (ref "LED8") (pin "3") (pinfunction "VSS_3") (pintype "input"))
      (node (ref "LED9") (pin "3") (pinfunction "VSS_3") (pintype "input"))
      (node (ref "Q5") (pin "1") (pinfunction "ADJ/GND_1") (pintype "input"))
      (node (ref "R1") (pin "1") (pinfunction "1_1") (pintype "input"))
      (node (ref "R2") (pin "2") (pinfunction "2_2") (pintype "input"))
      (node (ref "R4") (pin "1") (pinfunction "1_1") (pintype "input"))
      (node (ref "U1") (pin "1") (pinfunction "GND_1") (pintype "input"))
      (node (ref "U1") (pin "15") (pinfunction "GND_15") (pintype "input"))
      (node (ref "U1") (pin "38") (pinfunction "GND_38") (pintype "input"))
      (node (ref "U1") (pin "39") (pinfunction "EP_39") (pintype "input"))
      (node (ref "U2") (pin "1") (pinfunction "GND_1") (pintype "input"))
      (node (ref "U8") (pin "2") (pinfunction "ADDR_2") (pintype "input"))
      (node (ref "U8") (pin "7") (pinfunction "R_7") (pintype "input"))
      (node (ref "U8") (pin "8") (pinfunction "VSS_8") (pintype "input"))
      (node (ref "U8") (pin "9") (pinfunction "EP_9") (pintype "input"))
      (node (ref "U9") (pin "4") (pinfunction "GND_4") (pintype "input"))
      (node (ref "USB1") (pin "A1") (pinfunction "GND_A1") (pintype "input"))
      (node (ref "USB1") (pin "A12") (pinfunction "GND_A12") (pintype "input"))
      (node (ref "USB1") (pin "B1") (pinfunction "GND_B1") (pintype "input"))
      (node (ref "USB1") (pin "B12") (pinfunction "GND_B12") (pintype "input"))
    )
    (net (code "15") (name "Net-(LED1-DOUT)") (class "Default")
      (node (ref "LED1") (pin "2") (pinfunction "DOUT_2") (pintype "input"))
      (node (ref "LED2") (pin "4") (pinfunction "DIN_4") (pintype "input"))
    )
    (net (code "16") (name "Net-(LED2-DOUT)") (class "Default")
      (node (ref "LED2") (pin "2") (pinfunction "DOUT_2") (pintype "input"))
      (node (ref "LED3") (pin "4") (pinfunction "DIN_4") (pintype "input"))
    )
    (net (code "17") (name "Net-(LED3-DOUT)") (class "Default")
      (node (ref "LED3") (pin "2") (pinfunction "DOUT_2") (pintype "input"))
      (node (ref "LED4") (pin "4") (pinfunction "DIN_4") (pintype "input"))
    )
    (net (code "18") (name "Net-(LED4-DOUT)") (class "Default")
      (node (ref "LED4") (pin "2") (pinfunction "DOUT_2") (pintype "input"))
      (node (ref "LED5") (pin "4") (pinfunction "DIN_4") (pintype "input"))
    )
    (net (code "19") (name "Net-(LED5-DOUT)") (class "Default")
      (node (ref "LED5") (pin "2") (pinfunction "DOUT_2") (pintype "input"))
      (node (ref "LED6") (pin "4") (pinfunction "DIN_4") (pintype "input"))
    )
    (net (code "20") (name "Net-(LED6-DOUT)") (class "Default")
      (node (ref "LED6") (pin "2") (pinfunction "DOUT_2") (pintype "input"))
      (node (ref "LED7") (pin "4") (pinfunction "DIN_4") (pintype "input"))
    )
    (net (code "21") (name "Net-(LED7-DOUT)") (class "Default")
      (node (ref "LED7") (pin "2") (pinfunction "DOUT_2") (pintype "input"))
      (node (ref "LED8") (pin "4") (pinfunction "DIN_4") (pintype "input"))
    )
    (net (code "22") (name "Net-(LED8-DOUT)") (class "Default")
      (node (ref "LED8") (pin "2") (pinfunction "DOUT_2") (pintype "input"))
      (node (ref "LED9") (pin "4") (pinfunction "DIN_4") (pintype "input"))
    )
    (net (code "23") (name "Net-(LED10-DIN)") (class "Default")
      (node (ref "LED10") (pin "4") (pinfunction "DIN_4") (pintype "input"))
      (node (ref "LED9") (pin "2") (pinfunction "DOUT_2") (pintype "input"))
    )
    (net (code "24") (name "Net-(LED10-DOUT)") (class "Default")
      (node (ref "LED10") (pin "2") (pinfunction "DOUT_2") (pintype "input"))
      (node (ref "LED11") (pin "4") (pinfunction "DIN_4") (pintype "input"))
    )
    (net (code "25") (name "Net-(LED11-DOUT)") (class "Default")
      (node (ref "LED11") (pin "2") (pinfunction "DOUT_2") (pintype "input"))
      (node (ref "LED12") (pin "4") (pinfunction "DIN_4") (pintype "input"))
    )
    (net (code "26") (name "Net-(LED12-DOUT)") (class "Default")
      (node (ref "LED12") (pin "2") (pinfunction "DOUT_2") (pintype "input"))
      (node (ref "LED13") (pin "4") (pinfunction "DIN_4") (pintype "input"))
    )
    (net (code "27") (name "Net-(LED13-DOUT)") (class "Default")
      (node (ref "LED13") (pin "2") (pinfunction "DOUT_2") (pintype "input"))
      (node (ref "LED14") (pin "4") (pinfunction "DIN_4") (pintype "input"))
    )
    (net (code "28") (name "Net-(LED14-DOUT)") (class "Default")
      (node (ref "LED14") (pin "2") (pinfunction "DOUT_2") (pintype "input"))
      (node (ref "LED15") (pin "4") (pinfunction "DIN_4") (pintype "input"))
    )
    (net (code "29") (name "Net-(LED15-DOUT)") (class "Default")
      (node (ref "LED15") (pin "2") (pinfunction "DOUT_2") (pintype "input"))
      (node (ref "LED16") (pin "4") (pinfunction "DIN_4") (pintype "input"))
    )
    (net (code "30") (name "Net-(LED16-DOUT)") (class "Default")
      (node (ref "LED16") (pin "2") (pinfunction "DOUT_2") (pintype "input"))
      (node (ref "LED17") (pin "4") (pinfunction "DIN_4") (pintype "input"))
    )
    (net (code "31") (name "Net-(LED17-DOUT)") (class "Default")
      (node (ref "LED17") (pin "2") (pinfunction "DOUT_2") (pintype "input"))
      (node (ref "LED18") (pin "4") (pinfunction "DIN_4") (pintype "input"))
    )
    (net (code "32") (name "Net-(LED18-DOUT)") (class "Default")
      (node (ref "LED18") (pin "2") (pinfunction "DOUT_2") (pintype "input"))
      (node (ref "LED19") (pin "4") (pinfunction "DIN_4") (pintype "input"))
    )
    (net (code "33") (name "Net-(LED19-DOUT)") (class "Default")
      (node (ref "LED19") (pin "2") (pinfunction "DOUT_2") (pintype "input"))
      (node (ref "LED20") (pin "4") (pinfunction "DIN_4") (pintype "input"))
    )
    (net (code "34") (name "Net-(LED20-DOUT)") (class "Default")
      (node (ref "LED20") (pin "2") (pinfunction "DOUT_2") (pintype "input"))
      (node (ref "LED21") (pin "4") (pinfunction "DIN_4") (pintype "input"))
    )
    (net (code "35") (name "Net-(LED21-DOUT)") (class "Default")
      (node (ref "LED21") (pin "2") (pinfunction "DOUT_2") (pintype "input"))
      (node (ref "LED22") (pin "4") (pinfunction "DIN_4") (pintype "input"))
    )
    (net (code "36") (name "Net-(LED22-DOUT)") (class "Default")
      (node (ref "LED22") (pin "2") (pinfunction "DOUT_2") (pintype "input"))
      (node (ref "LED23") (pin "4") (pinfunction "DIN_4") (pintype "input"))
    )
    (net (code "37") (name "Net-(LED23-DOUT)") (class "Default")
      (node (ref "LED23") (pin "2") (pinfunction "DOUT_2") (pintype "input"))
      (node (ref "LED24") (pin "4") (pinfunction "DIN_4") (pintype "input"))
    )
    (net (code "38") (name "Net-(LED24-DOUT)") (class "Default")
      (node (ref "LED24") (pin "2") (pinfunction "DOUT_2") (pintype "input"))
      (node (ref "LED25") (pin "4") (pinfunction "DIN_4") (pintype "input"))
    )
    (net (code "39") (name "Net-(LED25-DOUT)") (class "Default")
      (node (ref "LED25") (pin "2") (pinfunction "DOUT_2") (pintype "input"))
      (node (ref "LED26") (pin "4") (pinfunction "DIN_4") (pintype "input"))
    )
    (net (code "40") (name "Net-(LED26-DOUT)") (class "Default")
      (node (ref "LED26") (pin "2") (pinfunction "DOUT_2") (pintype "input"))
      (node (ref "LED27") (pin "4") (pinfunction "DIN_4") (pintype "input"))
    )
    (net (code "41") (name "Net-(LED27-DOUT)") (class "Default")
      (node (ref "LED27") (pin "2") (pinfunction "DOUT_2") (pintype "input"))
      (node (ref "LED28") (pin "4") (pinfunction "DIN_4") (pintype "input"))
    )
    (net (code "42") (name "Net-(LED28-DOUT)") (class "Default")
      (node (ref "LED28") (pin "2") (pinfunction "DOUT_2") (pintype "input"))
      (node (ref "LED29") (pin "4") (pinfunction "DIN_4") (pintype "input"))
    )
    (net (code "43") (name "Net-(LED29-DOUT)") (class "Default")
      (node (ref "LED29") (pin "2") (pinfunction "DOUT_2") (pintype "input"))
      (node (ref "LED30") (pin "4") (pinfunction "DIN_4") (pintype "input"))
    )
    (net (code "44") (name "Net-(LED30-DOUT)") (class "Default")
      (node (ref "LED30") (pin "2") (pinfunction "DOUT_2") (pintype "input"))
      (node (ref "LED31") (pin "4") (pinfunction "DIN_4") (pintype "input"))
    )
    (net (code "45") (name "Net-(LED31-DOUT)") (class "Default")
      (node (ref "LED31") (pin "2") (pinfunction "DOUT_2") (pintype "input"))
      (node (ref "LED32") (pin "4") (pinfunction "DIN_4") (pintype "input"))
    )
    (net (code "46") (name "Net-(LED32-DOUT)") (class "Default")
      (node (ref "LED32") (pin "2") (pinfunction "DOUT_2") (pintype "input"))
      (node (ref "LED33") (pin "4") (pinfunction "DIN_4") (pintype "input"))
    )
    (net (code "47") (name "Net-(LED33-DOUT)") (class "Default")
      (node (ref "LED33") (pin "2") (pinfunction "DOUT_2") (pintype "input"))
      (node (ref "LED34") (pin "4") (pinfunction "DIN_4") (pintype "input"))
    )
    (net (code "48") (name "Net-(LED34-DOUT)") (class "Default")
      (node (ref "LED34") (pin "2") (pinfunction "DOUT_2") (pintype "input"))
      (node (ref "LED35") (pin "4") (pinfunction "DIN_4") (pintype "input"))
    )
    (net (code "49") (name "Net-(LED35-DOUT)") (class "Default")
      (node (ref "LED35") (pin "2") (pinfunction "DOUT_2") (pintype "input"))
      (node (ref "LED36") (pin "4") (pinfunction "DIN_4") (pintype "input"))
    )
    (net (code "50") (name "Net-(LED36-DOUT)") (class "Default")
      (node (ref "LED36") (pin "2") (pinfunction "DOUT_2") (pintype "input"))
      (node (ref "LED37") (pin "4") (pinfunction "DIN_4") (pintype "input"))
    )
    (net (code "51") (name "Net-(LED37-DOUT)") (class "Default")
      (node (ref "LED37") (pin "2") (pinfunction "DOUT_2") (pintype "input"))
      (node (ref "LED38") (pin "4") (pinfunction "DIN_4") (pintype "input"))
    )
    (net (code "52") (name "Net-(LED38-DOUT)") (class "Default")
      (node (ref "LED38") (pin "2") (pinfunction "DOUT_2") (pintype "input"))
      (node (ref "LED39") (pin "4") (pinfunction "DIN_4") (pintype "input"))
    )
    (net (code "53") (name "Net-(LED39-DOUT)") (class "Default")
      (node (ref "LED39") (pin "2") (pinfunction "DOUT_2") (pintype "input"))
      (node (ref "LED40") (pin "4") (pinfunction "DIN_4") (pintype "input"))
    )
    (net (code "54") (name "Net-(LED40-DOUT)") (class "Default")
      (node (ref "LED40") (pin "2") (pinfunction "DOUT_2") (pintype "input"))
      (node (ref "LED41") (pin "4") (pinfunction "DIN_4") (pintype "input"))
    )
    (net (code "55") (name "Net-(LED41-DOUT)") (class "Default")
      (node (ref "LED41") (pin "2") (pinfunction "DOUT_2") (pintype "input"))
      (node (ref "LED42") (pin "4") (pinfunction "DIN_4") (pintype "input"))
    )
    (net (code "56") (name "Net-(LED42-DOUT)") (class "Default")
      (node (ref "LED42") (pin "2") (pinfunction "DOUT_2") (pintype "input"))
      (node (ref "LED43") (pin "4") (pinfunction "DIN_4") (pintype "input"))
    )
    (net (code "57") (name "Net-(LED43-DOUT)") (class "Default")
      (node (ref "LED43") (pin "2") (pinfunction "DOUT_2") (pintype "input"))
      (node (ref "LED44") (pin "4") (pinfunction "DIN_4") (pintype "input"))
    )
    (net (code "58") (name "Net-(LED44-DOUT)") (class "Default")
      (node (ref "LED44") (pin "2") (pinfunction "DOUT_2") (pintype "input"))
      (node (ref "LED45") (pin "4") (pinfunction "DIN_4") (pintype "input"))
    )
    (net (code "59") (name "Net-(LED45-DOUT)") (class "Default")
      (node (ref "LED45") (pin "2") (pinfunction "DOUT_2") (pintype "input"))
      (node (ref "LED46") (pin "4") (pinfunction "DIN_4") (pintype "input"))
    )
    (net (code "60") (name "Net-(LED46-DOUT)") (class "Default")
      (node (ref "LED46") (pin "2") (pinfunction "DOUT_2") (pintype "input"))
      (node (ref "LED47") (pin "4") (pinfunction "DIN_4") (pintype "input"))
    )
    (net (code "61") (name "Net-(LED47-DOUT)") (class "Default")
      (node (ref "LED47") (pin "2") (pinfunction "DOUT_2") (pintype "input"))
      (node (ref "LED48") (pin "4") (pinfunction "DIN_4") (pintype "input"))
    )
    (net (code "62") (name "Net-(LED48-DOUT)") (class "Default")
      (node (ref "LED48") (pin "2") (pinfunction "DOUT_2") (pintype "input"))
      (node (ref "LED49") (pin "4") (pinfunction "DIN_4") (pintype "input"))
    )
    (net (code "63") (name "Net-(LED49-DOUT)") (class "Default")
      (node (ref "LED49") (pin "2") (pinfunction "DOUT_2") (pintype "input"))
      (node (ref "LED50") (pin "4") (pinfunction "DIN_4") (pintype "input"))
    )
    (net (code "64") (name "Net-(LED50-DOUT)") (class "Default")
      (node (ref "LED50") (pin "2") (pinfunction "DOUT_2") (pintype "input"))
      (node (ref "LED51") (pin "4") (pinfunction "DIN_4") (pintype "input"))
    )
    (net (code "65") (name "Net-(LED51-DOUT)") (class "Default")
      (node (ref "LED51") (pin "2") (pinfunction "DOUT_2") (pintype "input"))
      (node (ref "LED52") (pin "4") (pinfunction "DIN_4") (pintype "input"))
    )
    (net (code "66") (name "Net-(LED52-DOUT)") (class "Default")
      (node (ref "LED52") (pin "2") (pinfunction "DOUT_2") (pintype "input"))
      (node (ref "LED53") (pin "4") (pinfunction "DIN_4") (pintype "input"))
    )
    (net (code "67") (name "Net-(LED53-DOUT)") (class "Default")
      (node (ref "LED53") (pin "2") (pinfunction "DOUT_2") (pintype "input"))
      (node (ref "LED54") (pin "4") (pinfunction "DIN_4") (pintype "input"))
    )
    (net (code "68") (name "Net-(LED54-DOUT)") (class "Default")
      (node (ref "LED54") (pin "2") (pinfunction "DOUT_2") (pintype "input"))
      (node (ref "LED55") (pin "4") (pinfunction "DIN_4") (pintype "input"))
    )
    (net (code "69") (name "Net-(LED55-DOUT)") (class "Default")
      (node (ref "LED55") (pin "2") (pinfunction "DOUT_2") (pintype "input"))
      (node (ref "LED56") (pin "4") (pinfunction "DIN_4") (pintype "input"))
    )
    (net (code "70") (name "Net-(LED56-DOUT)") (class "Default")
      (node (ref "LED56") (pin "2") (pinfunction "DOUT_2") (pintype "input"))
      (node (ref "LED57") (pin "4") (pinfunction "DIN_4") (pintype "input"))
    )
    (net (code "71") (name "Net-(LED57-DOUT)") (class "Default")
      (node (ref "LED57") (pin "2") (pinfunction "DOUT_2") (pintype "input"))
      (node (ref "LED58") (pin "4") (pinfunction "DIN_4") (pintype "input"))
    )
    (net (code "72") (name "Net-(LED58-DOUT)") (class "Default")
      (node (ref "LED58") (pin "2") (pinfunction "DOUT_2") (pintype "input"))
      (node (ref "LED59") (pin "4") (pinfunction "DIN_4") (pintype "input"))
    )
    (net (code "73") (name "Net-(LED59-DOUT)") (class "Default")
      (node (ref "LED59") (pin "2") (pinfunction "DOUT_2") (pintype "input"))
      (node (ref "LED60") (pin "4") (pinfunction "DIN_4") (pintype "input"))
    )
    (net (code "74") (name "Net-(LED60-DOUT)") (class "Default")
      (node (ref "LED60") (pin "2") (pinfunction "DOUT_2") (pintype "input"))
      (node (ref "LED61") (pin "4") (pinfunction "DIN_4") (pintype "input"))
    )
    (net (code "75") (name "Net-(LED61-DOUT)") (class "Default")
      (node (ref "LED61") (pin "2") (pinfunction "DOUT_2") (pintype "input"))
      (node (ref "LED62") (pin "4") (pinfunction "DIN_4") (pintype "input"))
    )
    (net (code "76") (name "Net-(LED62-DOUT)") (class "Default")
      (node (ref "LED62") (pin "2") (pinfunction "DOUT_2") (pintype "input"))
      (node (ref "LED63") (pin "4") (pinfunction "DIN_4") (pintype "input"))
    )
    (net (code "77") (name "Net-(LED63-DOUT)") (class "Default")
      (node (ref "LED63") (pin "2") (pinfunction "DOUT_2") (pintype "input"))
      (node (ref "LED64") (pin "4") (pinfunction "DIN_4") (pintype "input"))
    )
    (net (code "78") (name "Net-(U1-IO2)") (class "Default")
      (node (ref "R4") (pin "2") (pinfunction "2_2") (pintype "input"))
      (node (ref "U1") (pin "24") (pinfunction "IO2_24") (pintype "input"))
    )
    (net (code "79") (name "Net-(U9-VCC1)") (class "Default")
      (node (ref "C105") (pin "1") (pinfunction "1_1") (pintype "input"))
      (node (ref "U9") (pin "8") (pinfunction "VCC1_8") (pintype "input"))
    )
    (net (code "80") (name "Net-(U9-X1)") (class "Default")
      (node (ref "U9") (pin "2") (pinfunction "X1_2") (pintype "input"))
      (node (ref "X1") (pin "1") (pinfunction "OSC1_1") (pintype "input"))
    )
    (net (code "81") (name "Net-(U9-X2)") (class "Default")
      (node (ref "U9") (pin "3") (pinfunction "X2_3") (pintype "input"))
      (node (ref "X1") (pin "4") (pinfunction "OSC2_4") (pintype "input"))
    )
    (net (code "82") (name "Net-(USB1-CC1)") (class "Default")
      (node (ref "R2") (pin "1") (pinfunction "1_1") (pintype "input"))
      (node (ref "USB1") (pin "A5") (pinfunction "CC1_A5") (pintype "input"))
    )
    (net (code "83") (name "Net-(USB1-CC2)") (class "Default")
      (node (ref "R1") (pin "2") (pinfunction "2_2") (pintype "input"))
      (node (ref "USB1") (pin "B5") (pinfunction "CC2_B5") (pintype "input"))
    )
    (net (code "84") (name "RTS") (class "Default")
      (node (ref "Q1") (pin "1") (pinfunction "E_1") (pintype "input"))
      (node (ref "Q1") (pin "5") (pinfunction "B_5") (pintype "input"))
      (node (ref "U2") (pin "14") (pinfunction "RTS#_14") (pintype "input"))
    )
    (net (code "85") (name "SHT_SCL") (class "Default")
      (node (ref "R27") (pin "1") (pinfunction "1_1") (pintype "input"))
      (node (ref "U1") (pin "11") (pinfunction "IO26_11") (pintype "input"))
      (node (ref "U8") (pin "4") (pinfunction "SCL_4") (pintype "input"))
    )
    (net (code "86") (name "SHT_SDA") (class "Default")
      (node (ref "R26") (pin "1") (pinfunction "1_1") (pintype "input"))
      (node (ref "U1") (pin "12") (pinfunction "IO27_12") (pintype "input"))
      (node (ref "U8") (pin "1") (pinfunction "SDA_1") (pintype "input"))
    )
    (net (code "87") (name "VCC") (class "Default")
      (node (ref "C104") (pin "2") (pinfunction "2_2") (pintype "input"))
      (node (ref "D1") (pin "1") (pinfunction "K_1") (pintype "input"))
      (node (ref "Q5") (pin "3") (pinfunction "VIN_3") (pintype "input"))
      (node (ref "R5") (pin "1") (pinfunction "1_1") (pintype "input"))
    )
    (net (code "88") (name "VLED") (class "Default")
      (node (ref "C2") (pin "2") (pinfunction "2_2") (pintype "input"))
      (node (ref "C3") (pin "2") (pinfunction "2_2") (pintype "input"))
      (node (ref "C4") (pin "2") (pinfunction "2_2") (pintype "input"))
      (node (ref "C5") (pin "2") (pinfunction "2_2") (pintype "input"))
      (node (ref "C6") (pin "2") (pinfunction "2_2") (pintype "input"))
      (node (ref "C7") (pin "2") (pinfunction "2_2") (pintype "input"))
      (node (ref "C8") (pin "2") (pinfunction "2_2") (pintype "input"))
      (node (ref "C9") (pin "2") (pinfunction "2_2") (pintype "input"))
      (node (ref "LED1") (pin "1") (pinfunction "VDD_1") (pintype "input"))
      (node (ref "LED10") (pin "1") (pinfunction "VDD_1") (pintype "input"))
      (node (ref "LED11") (pin "1") (pinfunction "VDD_1") (pintype "input"))
      (node (ref "LED12") (pin "1") (pinfunction "VDD_1") (pintype "input"))
      (node (ref "LED13") (pin "1") (pinfunction "VDD_1") (pintype "input"))
      (node (ref "LED14") (pin "1") (pinfunction "VDD_1") (pintype "input"))
      (node (ref "LED15") (pin "1") (pinfunction "VDD_1") (pintype "input"))
      (node (ref "LED16") (pin "1") (pinfunction "VDD_1") (pintype "input"))
      (node (ref "LED17") (pin "1") (pinfunction "VDD_1") (pintype "input"))
      (node (ref "LED18") (pin "1") (pinfunction "VDD_1") (pintype "input"))
      (node (ref "LED19") (pin "1") (pinfunction "VDD_1") (pintype "input"))
      (node (ref "LED2") (pin "1") (pinfunction "VDD_1") (pintype "input"))
      (node (ref "LED20") (pin "1") (pinfunction "VDD_1") (pintype "input"))
      (node (ref "LED21") (pin "1") (pinfunction "VDD_1") (pintype "input"))
      (node (ref "LED22") (pin "1") (pinfunction "VDD_1") (pintype "input"))
      (node (ref "LED23") (pin "1") (pinfunction "VDD_1") (pintype "input"))
      (node (ref "LED24") (pin "1") (pinfunction "VDD_1") (pintype "input"))
      (node (ref "LED25") (pin "1") (pinfunction "VDD_1") (pintype "input"))
      (node (ref "LED26") (pin "1") (pinfunction "VDD_1") (pintype "input"))
      (node (ref "LED27") (pin "1") (pinfunction "VDD_1") (pintype "input"))
      (node (ref "LED28") (pin "1") (pinfunction "VDD_1") (pintype "input"))
      (node (ref "LED29") (pin "1") (pinfunction "VDD_1") (pintype "input"))
      (node (ref "LED3") (pin "1") (pinfunction "VDD_1") (pintype "input"))
      (node (ref "LED30") (pin "1") (pinfunction "VDD_1") (pintype "input"))
      (node (ref "LED31") (pin "1") (pinfunction "VDD_1") (pintype "input"))
      (node (ref "LED32") (pin "1") (pinfunction "VDD_1") (pintype "input"))
      (node (ref "LED33") (pin "1") (pinfunction "VDD_1") (pintype "input"))
      (node (ref "LED34") (pin "1") (pinfunction "VDD_1") (pintype "input"))
      (node (ref "LED35") (pin "1") (pinfunction "VDD_1") (pintype "input"))
      (node (ref "LED36") (pin "1") (pinfunction "VDD_1") (pintype "input"))
      (node (ref "LED37") (pin "1") (pinfunction "VDD_1") (pintype "input"))
      (node (ref "LED38") (pin "1") (pinfunction "VDD_1") (pintype "input"))
      (node (ref "LED39") (pin "1") (pinfunction "VDD_1") (pintype "input"))
      (node (ref "LED4") (pin "1") (pinfunction "VDD_1") (pintype "input"))
      (node (ref "LED40") (pin "1") (pinfunction "VDD_1") (pintype "input"))
      (node (ref "LED41") (pin "1") (pinfunction "VDD_1") (pintype "input"))
      (node (ref "LED42") (pin "1") (pinfunction "VDD_1") (pintype "input"))
      (node (ref "LED43") (pin "1") (pinfunction "VDD_1") (pintype "input"))
      (node (ref "LED44") (pin "1") (pinfunction "VDD_1") (pintype "input"))
      (node (ref "LED45") (pin "1") (pinfunction "VDD_1") (pintype "input"))
      (node (ref "LED46") (pin "1") (pinfunction "VDD_1") (pintype "input"))
      (node (ref "LED47") (pin "1") (pinfunction "VDD_1") (pintype "input"))
      (node (ref "LED48") (pin "1") (pinfunction "VDD_1") (pintype "input"))
      (node (ref "LED49") (pin "1") (pinfunction "VDD_1") (pintype "input"))
      (node (ref "LED5") (pin "1") (pinfunction "VDD_1") (pintype "input"))
      (node (ref "LED50") (pin "1") (pinfunction "VDD_1") (pintype "input"))
      (node (ref "LED51") (pin "1") (pinfunction "VDD_1") (pintype "input"))
      (node (ref "LED52") (pin "1") (pinfunction "VDD_1") (pintype "input"))
      (node (ref "LED53") (pin "1") (pinfunction "VDD_1") (pintype "input"))
      (node (ref "LED54") (pin "1") (pinfunction "VDD_1") (pintype "input"))
      (node (ref "LED55") (pin "1") (pinfunction "VDD_1") (pintype "input"))
      (node (ref "LED56") (pin "1") (pinfunction "VDD_1") (pintype "input"))
      (node (ref "LED57") (pin "1") (pinfunction "VDD_1") (pintype "input"))
      (node (ref "LED58") (pin "1") (pinfunction "VDD_1") (pintype "input"))
      (node (ref "LED59") (pin "1") (pinfunction "VDD_1") (pintype "input"))
      (node (ref "LED6") (pin "1") (pinfunction "VDD_1") (pintype "input"))
      (node (ref "LED60") (pin "1") (pinfunction "VDD_1") (pintype "input"))
      (node (ref "LED61") (pin "1") (pinfunction "VDD_1") (pintype "input"))
      (node (ref "LED62") (pin "1") (pinfunction "VDD_1") (pintype "input"))
      (node (ref "LED63") (pin "1") (pinfunction "VDD_1") (pintype "input"))
      (node (ref "LED64") (pin "1") (pinfunction "VDD_1") (pintype "input"))
      (node (ref "LED7") (pin "1") (pinfunction "VDD_1") (pintype "input"))
      (node (ref "LED8") (pin "1") (pinfunction "VDD_1") (pintype "input"))
      (node (ref "LED9") (pin "1") (pinfunction "VDD_1") (pintype "input"))
      (node (ref "R5") (pin "2") (pinfunction "2_2") (pintype "input"))
    )
    (net (code "89") (name "VUSB") (class "Default")
      (node (ref "D1") (pin "2") (pinfunction "A_2") (pintype "input"))
      (node (ref "USB1") (pin "A4") (pinfunction "VBUS_A4") (pintype "input"))
      (node (ref "USB1") (pin "A9") (pinfunction "VBUS_A9") (pintype "input"))
      (node (ref "USB1") (pin "B4") (pinfunction "VBUS_B4") (pintype "input"))
      (node (ref "USB1") (pin "B9") (pinfunction "VBUS_B9") (pintype "input"))
    )
    (net (code "90") (name "unconnected-(U1-CLK-Pad20)") (class "Default")
      (node (ref "U1") (pin "20") (pinfunction "CLK_20") (pintype "input"))
    )
    (net (code "91") (name "unconnected-(U1-CMD-Pad19)") (class "Default")
      (node (ref "U1") (pin "19") (pinfunction "CMD_19") (pintype "input"))
    )
    (net (code "92") (name "unconnected-(U1-IO4-Pad26)") (class "Default")
      (node (ref "U1") (pin "26") (pinfunction "IO4_26") (pintype "input"))
    )
    (net (code "93") (name "unconnected-(U1-IO5-Pad29)") (class "Default")
      (node (ref "U1") (pin "29") (pinfunction "IO5_29") (pintype "input"))
    )
    (net (code "94") (name "unconnected-(U1-IO12-Pad14)") (class "Default")
      (node (ref "U1") (pin "14") (pinfunction "IO12_14") (pintype "input"))
    )
    (net (code "95") (name "unconnected-(U1-IO13-Pad16)") (class "Default")
      (node (ref "U1") (pin "16") (pinfunction "IO13_16") (pintype "input"))
    )
    (net (code "96") (name "unconnected-(U1-IO14-Pad13)") (class "Default")
      (node (ref "U1") (pin "13") (pinfunction "IO14_13") (pintype "input"))
    )
    (net (code "97") (name "unconnected-(U1-IO15-Pad23)") (class "Default")
      (node (ref "U1") (pin "23") (pinfunction "IO15_23") (pintype "input"))
    )
    (net (code "98") (name "unconnected-(U1-IO16-Pad27)") (class "Default")
      (node (ref "U1") (pin "27") (pinfunction "IO16_27") (pintype "input"))
    )
    (net (code "99") (name "unconnected-(U1-IO17-Pad28)") (class "Default")
      (node (ref "U1") (pin "28") (pinfunction "IO17_28") (pintype "input"))
    )
    (net (code "100") (name "unconnected-(U1-IO18-Pad30)") (class "Default")
      (node (ref "U1") (pin "30") (pinfunction "IO18_30") (pintype "input"))
    )
    (net (code "101") (name "unconnected-(U1-IO19-Pad31)") (class "Default")
      (node (ref "U1") (pin "31") (pinfunction "IO19_31") (pintype "input"))
    )
    (net (code "102") (name "unconnected-(U1-IO21-Pad33)") (class "Default")
      (node (ref "U1") (pin "33") (pinfunction "IO21_33") (pintype "input"))
    )
    (net (code "103") (name "unconnected-(U1-IO22-Pad36)") (class "Default")
      (node (ref "U1") (pin "36") (pinfunction "IO22_36") (pintype "input"))
    )
    (net (code "104") (name "unconnected-(U1-IO34-Pad6)") (class "Default")
      (node (ref "U1") (pin "6") (pinfunction "IO34_6") (pintype "input"))
    )
    (net (code "105") (name "unconnected-(U1-IO35-Pad7)") (class "Default")
      (node (ref "U1") (pin "7") (pinfunction "IO35_7") (pintype "input"))
    )
    (net (code "106") (name "unconnected-(U1-NC-Pad32)") (class "Default")
      (node (ref "U1") (pin "32") (pinfunction "NC_32") (pintype "input"))
    )
    (net (code "107") (name "unconnected-(U1-SD2-Pad17)") (class "Default")
      (node (ref "U1") (pin "17") (pinfunction "SD2_17") (pintype "input"))
    )
    (net (code "108") (name "unconnected-(U1-SD3-Pad18)") (class "Default")
      (node (ref "U1") (pin "18") (pinfunction "SD3_18") (pintype "input"))
    )
    (net (code "109") (name "unconnected-(U1-SDI-Pad22)") (class "Default")
      (node (ref "U1") (pin "22") (pinfunction "SDI_22") (pintype "input"))
    )
    (net (code "110") (name "unconnected-(U1-SDO-Pad21)") (class "Default")
      (node (ref "U1") (pin "21") (pinfunction "SDO_21") (pintype "input"))
    )
    (net (code "111") (name "unconnected-(U1-SENSOR_VN-Pad5)") (class "Default")
      (node (ref "U1") (pin "5") (pinfunction "SENSOR_VN_5") (pintype "input"))
    )
    (net (code "112") (name "unconnected-(U1-SENSOR_VP-Pad4)") (class "Default")
      (node (ref "U1") (pin "4") (pinfunction "SENSOR_VP_4") (pintype "input"))
    )
    (net (code "113") (name "unconnected-(U2-CTS#-Pad9)") (class "Default")
      (node (ref "U2") (pin "9") (pinfunction "CTS#_9") (pintype "input+no_connect"))
    )
    (net (code "114") (name "unconnected-(U2-DCD#-Pad12)") (class "Default")
      (node (ref "U2") (pin "12") (pinfunction "DCD#_12") (pintype "input+no_connect"))
    )
    (net (code "115") (name "unconnected-(U2-DSR#-Pad10)") (class "Default")
      (node (ref "U2") (pin "10") (pinfunction "DSR#_10") (pintype "input+no_connect"))
    )
    (net (code "116") (name "unconnected-(U2-NC.-Pad7)") (class "Default")
      (node (ref "U2") (pin "7") (pinfunction "NC._7") (pintype "input+no_connect"))
    )
    (net (code "117") (name "unconnected-(U2-NC.-Pad8)") (class "Default")
      (node (ref "U2") (pin "8") (pinfunction "NC._8") (pintype "input+no_connect"))
    )
    (net (code "118") (name "unconnected-(U2-R232-Pad15)") (class "Default")
      (node (ref "U2") (pin "15") (pinfunction "R232_15") (pintype "input+no_connect"))
    )
    (net (code "119") (name "unconnected-(U2-RI#-Pad11)") (class "Default")
      (node (ref "U2") (pin "11") (pinfunction "RI#_11") (pintype "input+no_connect"))
    )
    (net (code "120") (name "unconnected-(U8-ALERT-Pad3)") (class "Default")
      (node (ref "U8") (pin "3") (pinfunction "ALERT_3") (pintype "input+no_connect"))
    )
    (net (code "121") (name "unconnected-(U8-nRESET-Pad6)") (class "Default")
      (node (ref "U8") (pin "6") (pinfunction "nRESET_6") (pintype "input+no_connect"))
    )
    (net (code "122") (name "unconnected-(USB1-EP-Pad1)") (class "Default")
      (node (ref "USB1") (pin "1") (pinfunction "EP_1") (pintype "input"))
    )
    (net (code "123") (name "unconnected-(USB1-EP-Pad2)") (class "Default")
      (node (ref "USB1") (pin "2") (pinfunction "EP_2") (pintype "input"))
    )
    (net (code "124") (name "unconnected-(USB1-EP-Pad3)") (class "Default")
      (node (ref "USB1") (pin "3") (pinfunction "EP_3") (pintype "input"))
    )
    (net (code "125") (name "unconnected-(USB1-EP-Pad4)") (class "Default")
      (node (ref "USB1") (pin "4") (pinfunction "EP_4") (pintype "input"))
    )
    (net (code "126") (name "unconnected-(USB1-SBU1-PadA8)") (class "Default")
      (node (ref "USB1") (pin "A8") (pinfunction "SBU1_A8") (pintype "input"))
    )
    (net (code "127") (name "unconnected-(USB1-SBU2-PadB8)") (class "Default")
      (node (ref "USB1") (pin "B8") (pinfunction "SBU2_B8") (pintype "input"))
    )
    (net (code "128") (name "unconnected-(X1-Pad2)") (class "Default")
      (node (ref "X1") (pin "2") (pinfunction "2_2") (pintype "input"))
    )
    (net (code "129") (name "unconnected-(X1-Pad3)") (class "Default")
      (node (ref "X1") (pin "3") (pinfunction "3_3") (pintype "input"))
    )
  )
)
